# module_alu1_ctrl.net
KiCad netlist of a schematic drawn in EAGLE
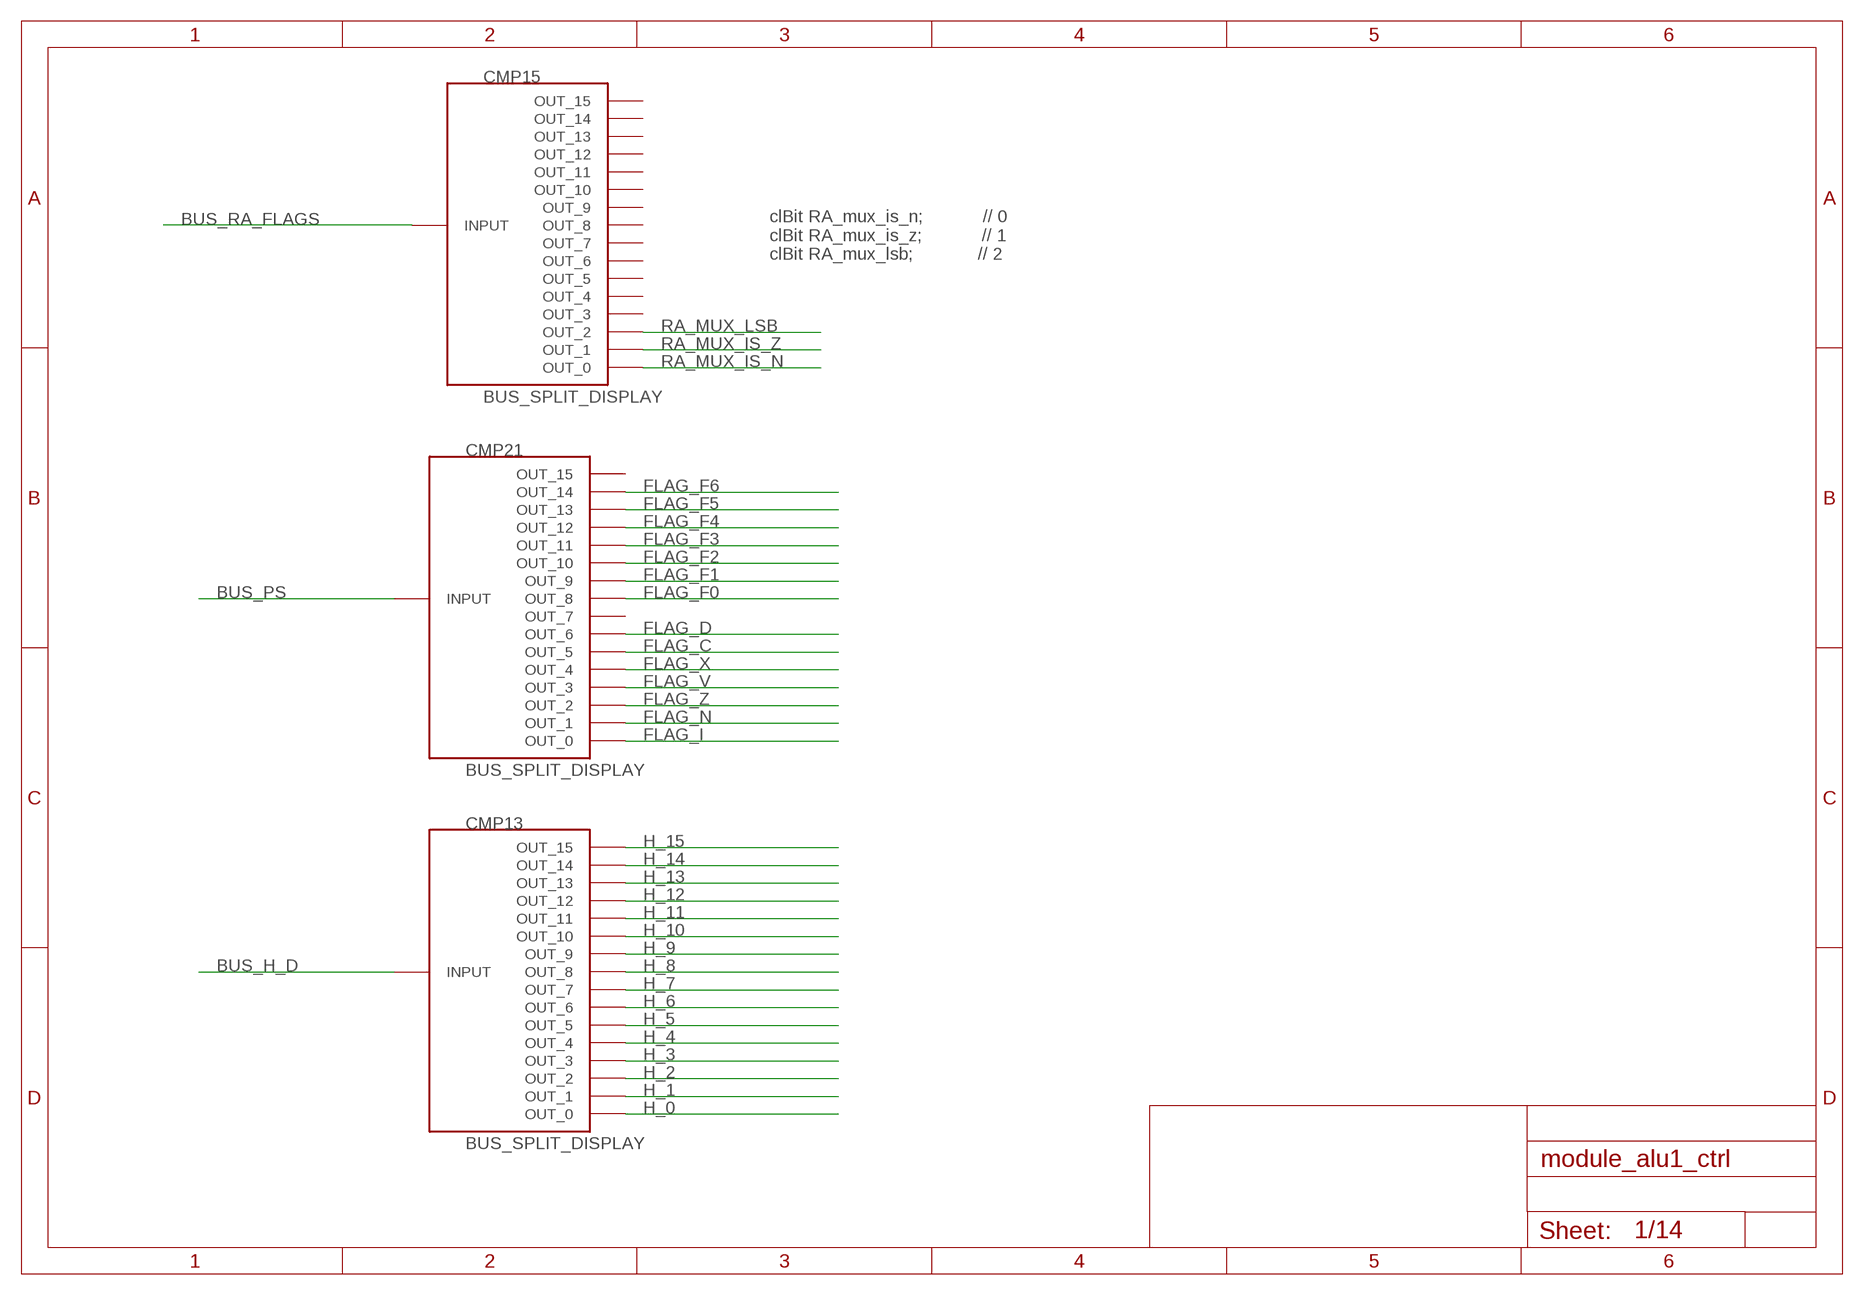
[diagram p0: schematic, sheet 1]
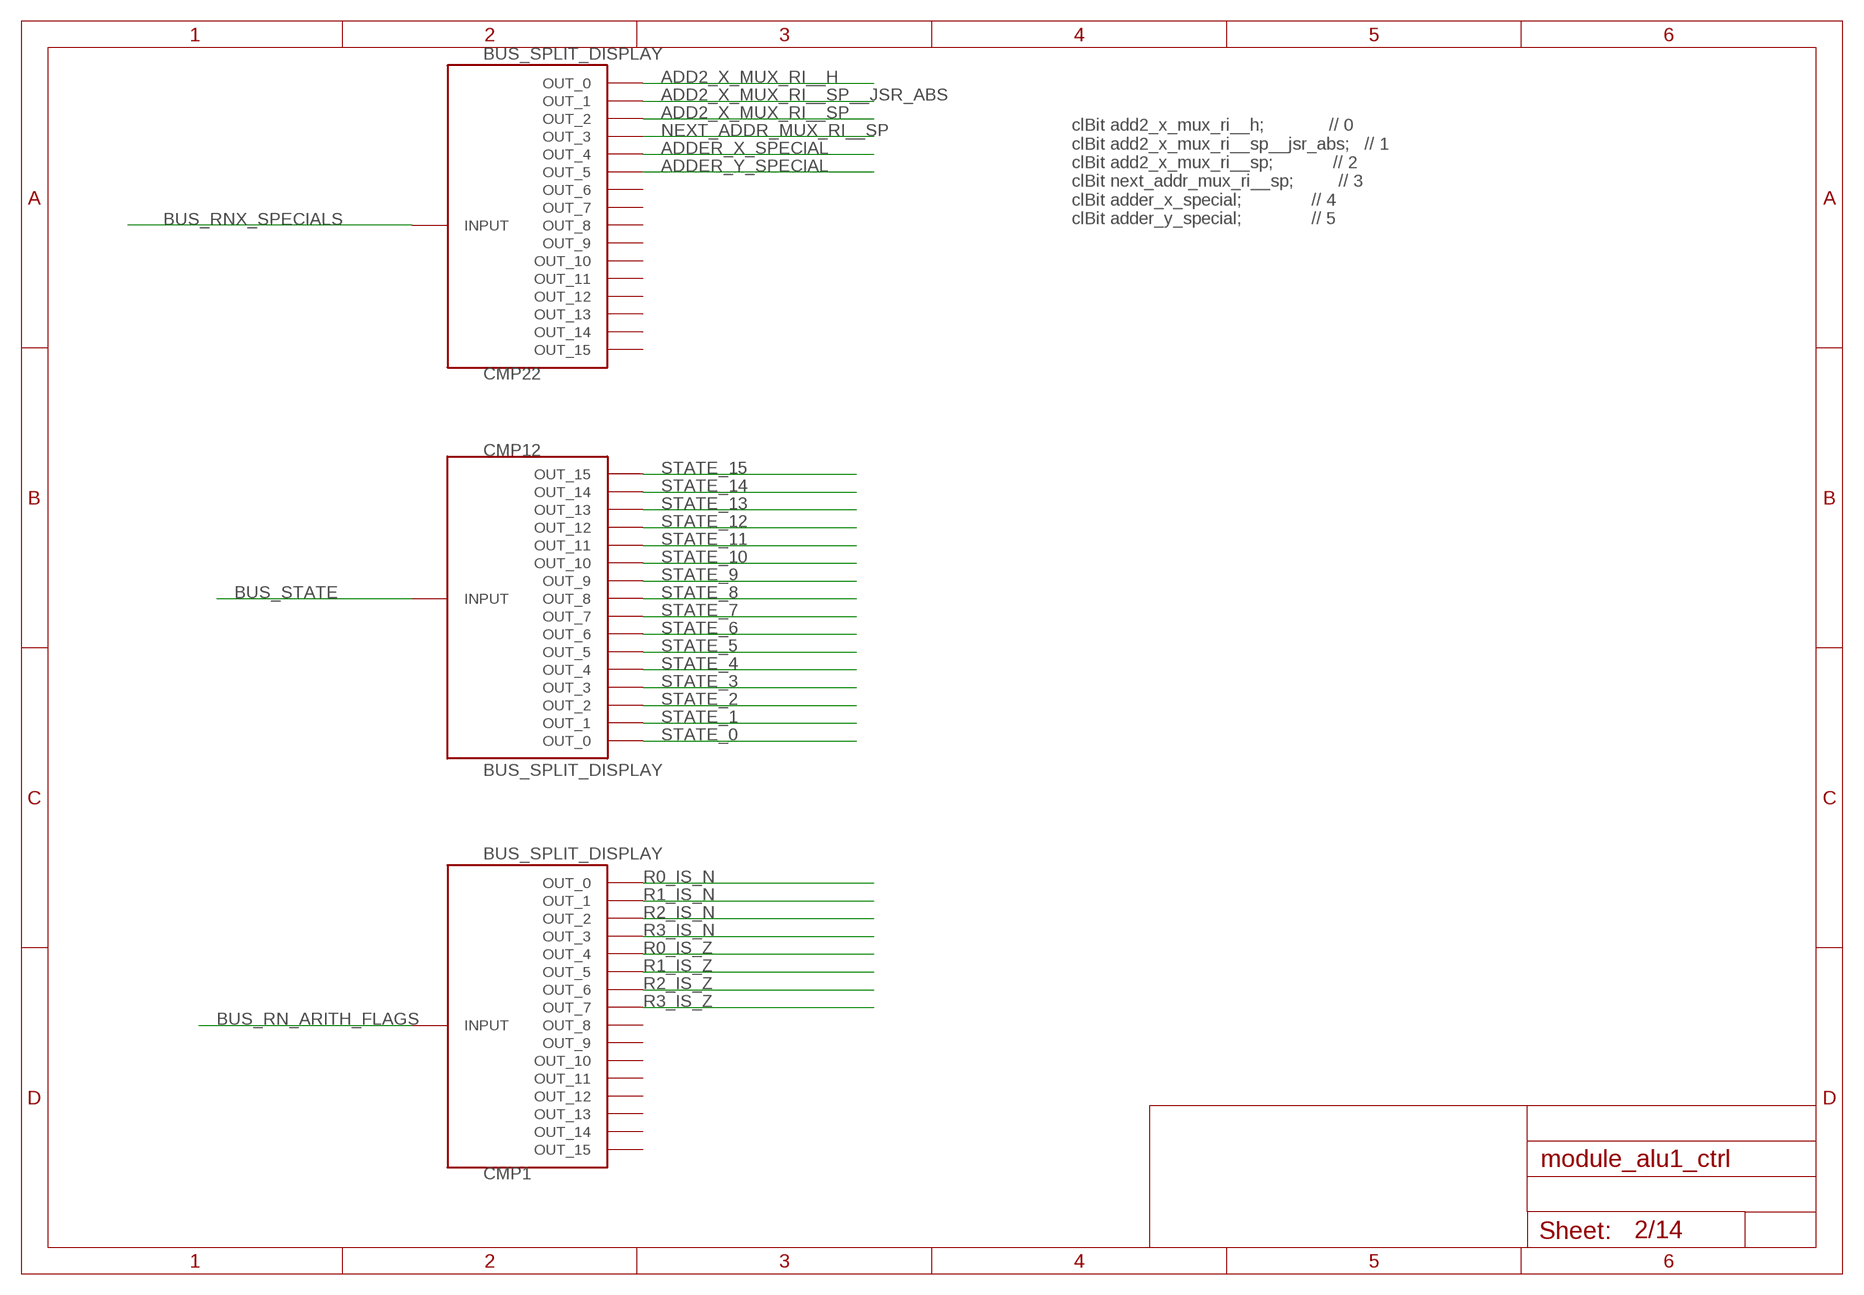
[diagram p1: schematic, sheet 2]
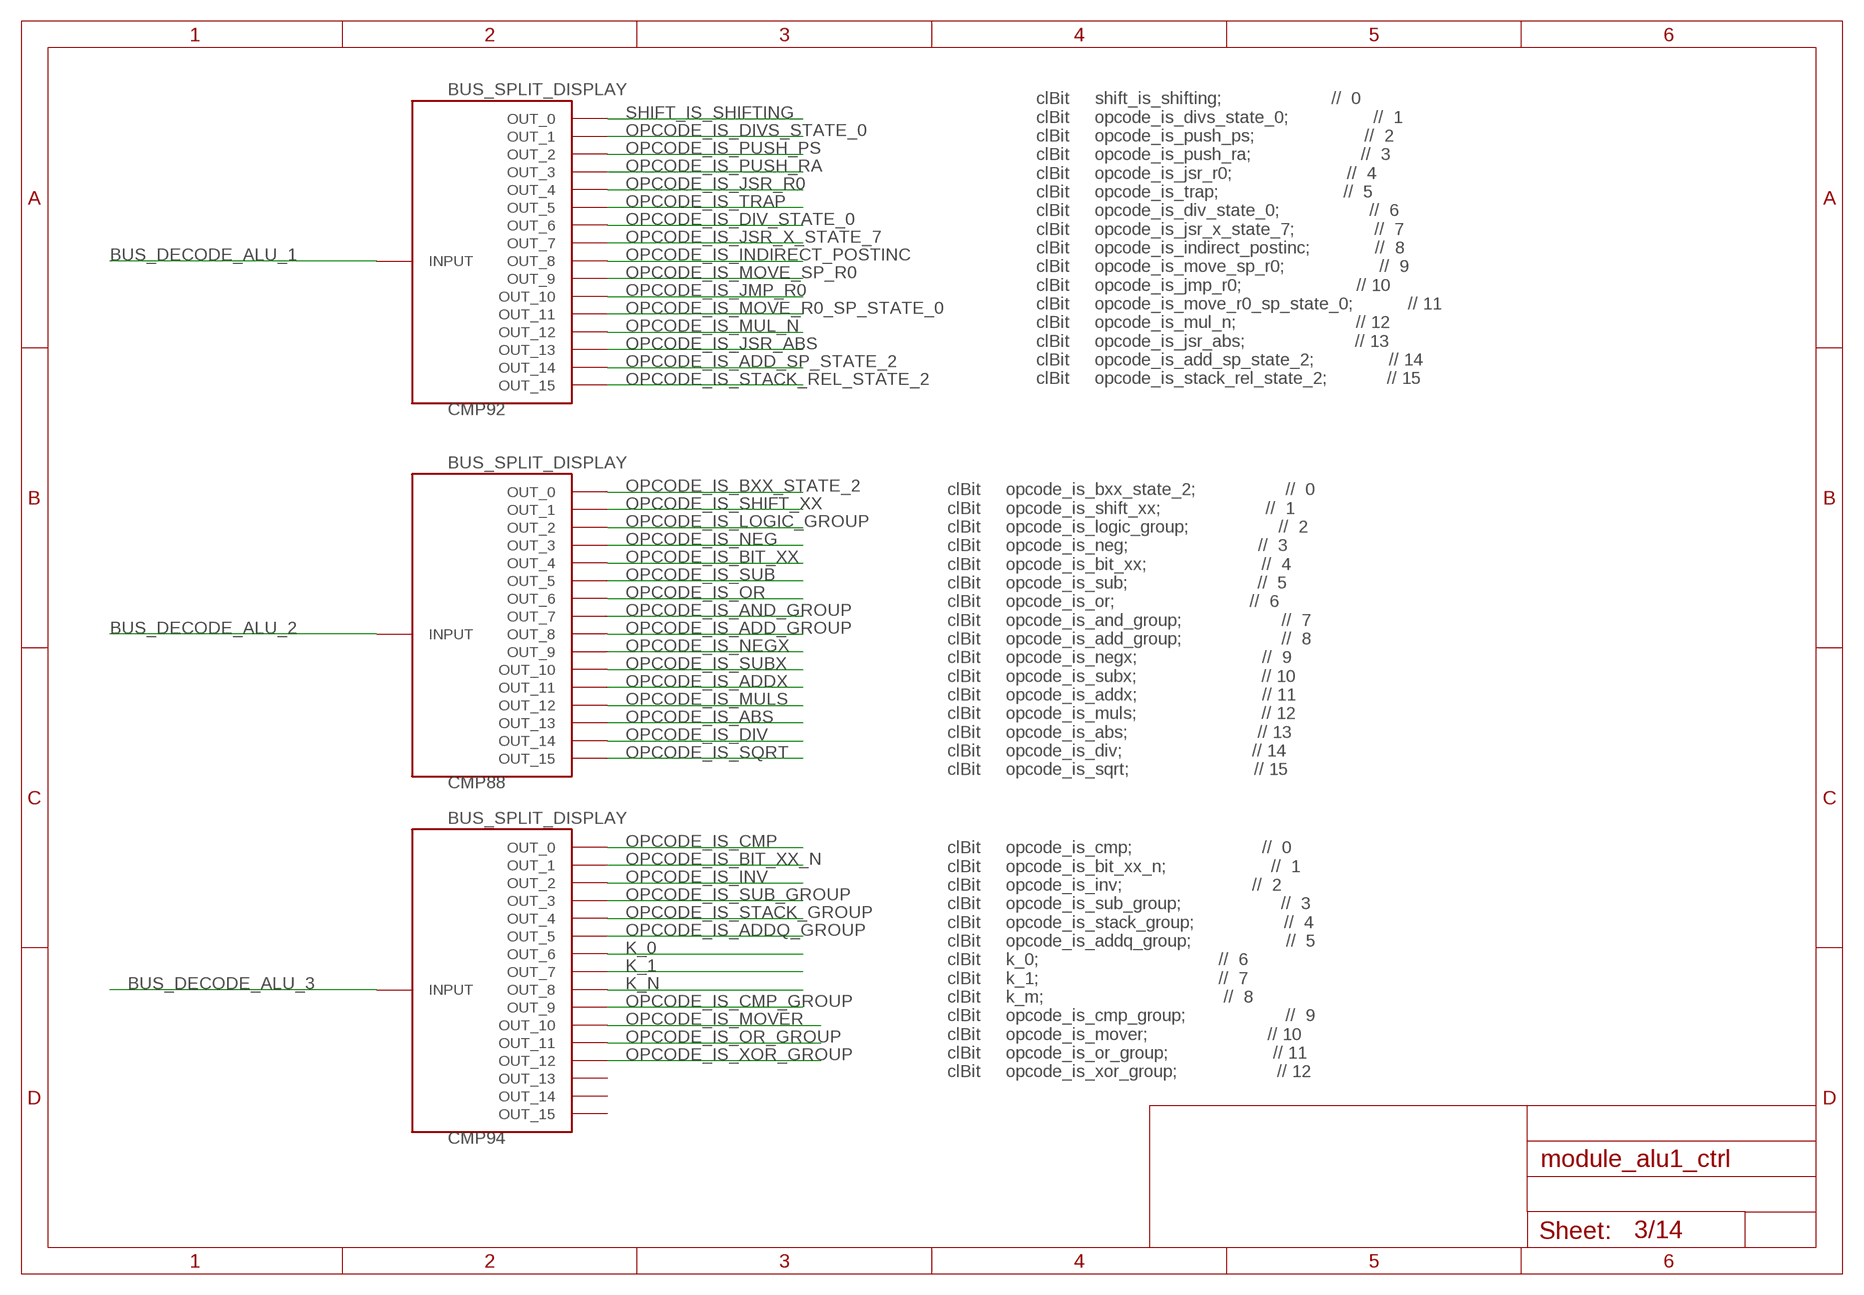
[diagram p2: schematic, sheet 3]
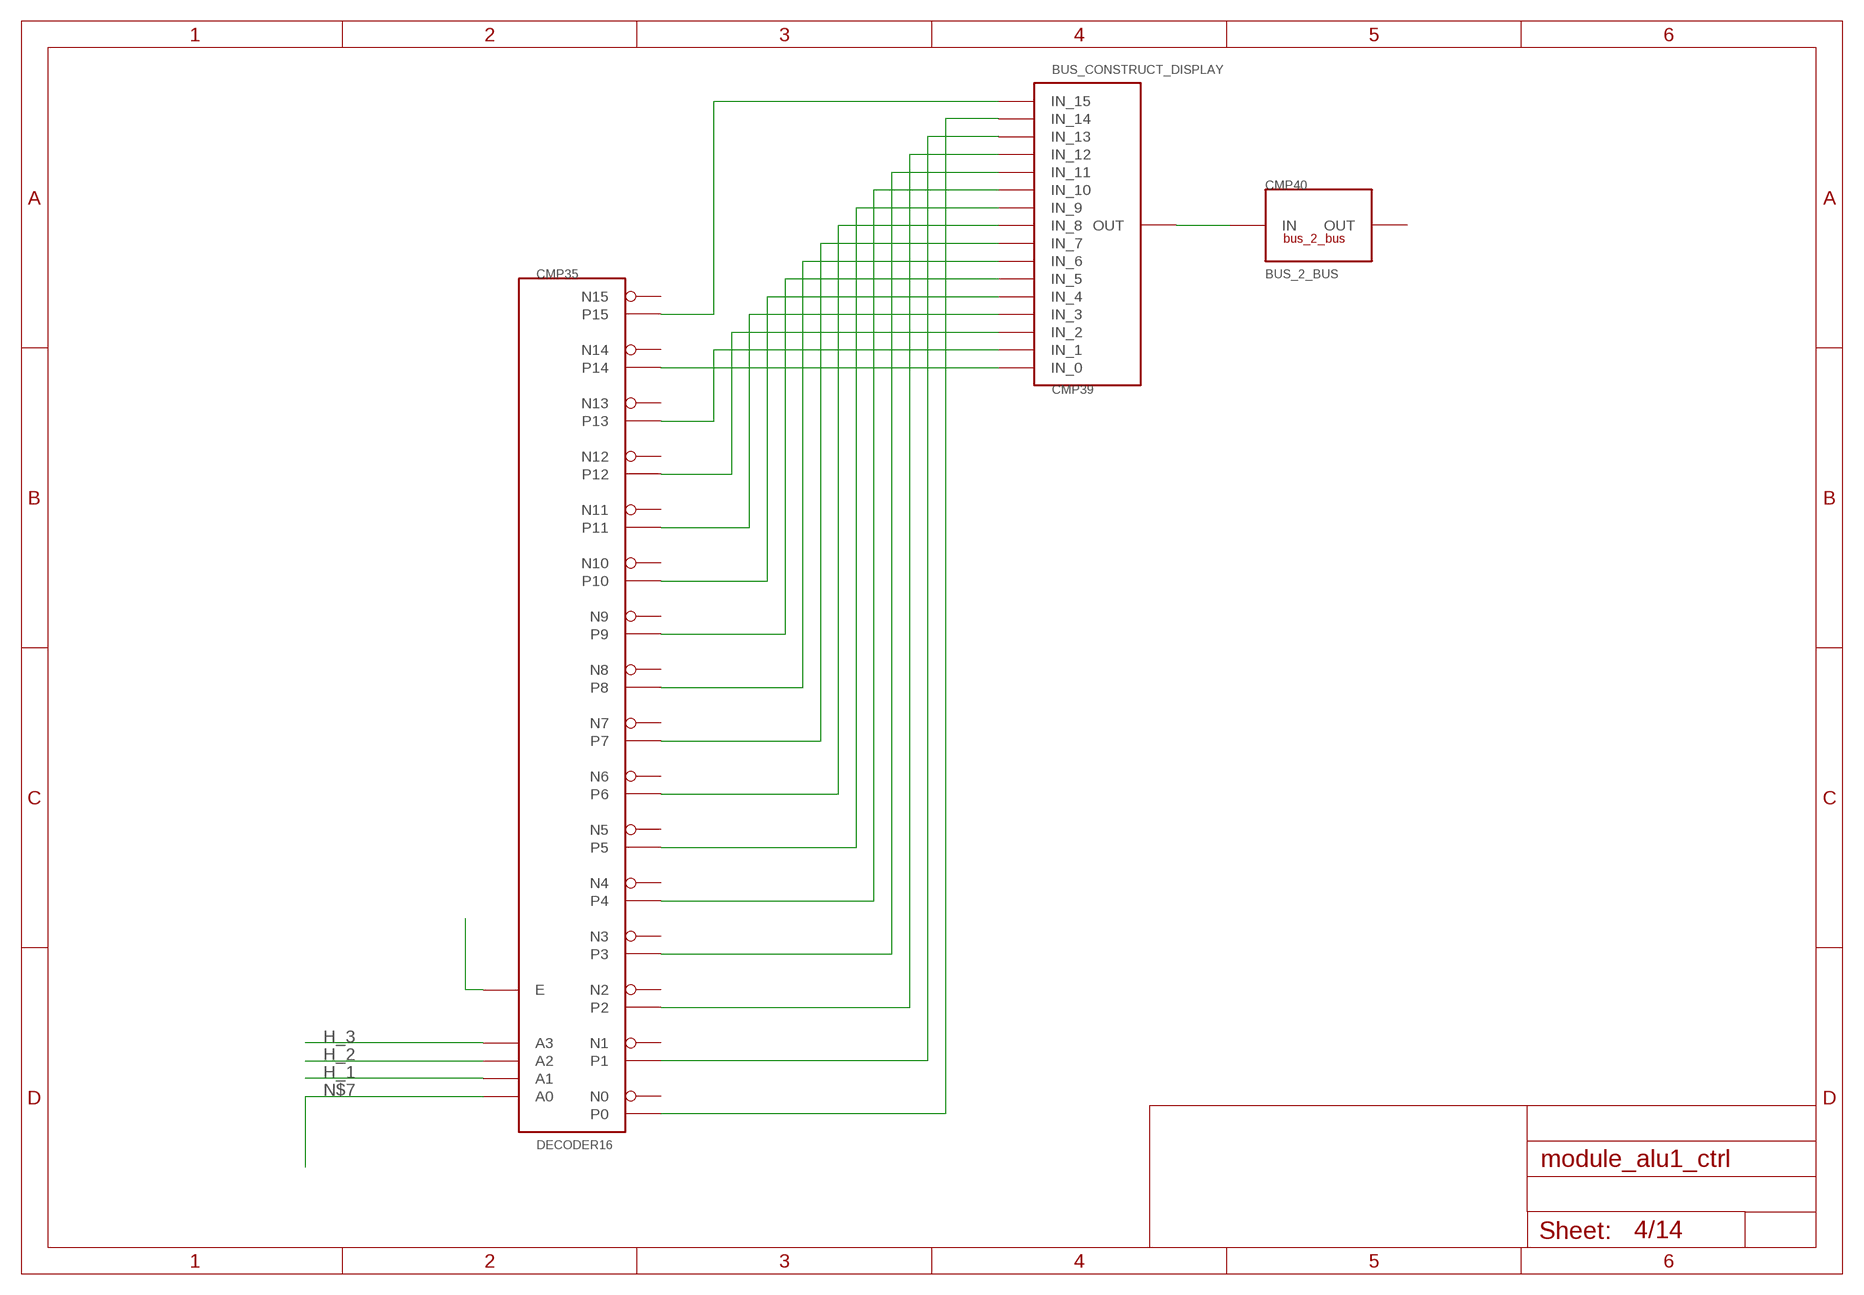
[diagram p3: schematic, sheet 4]
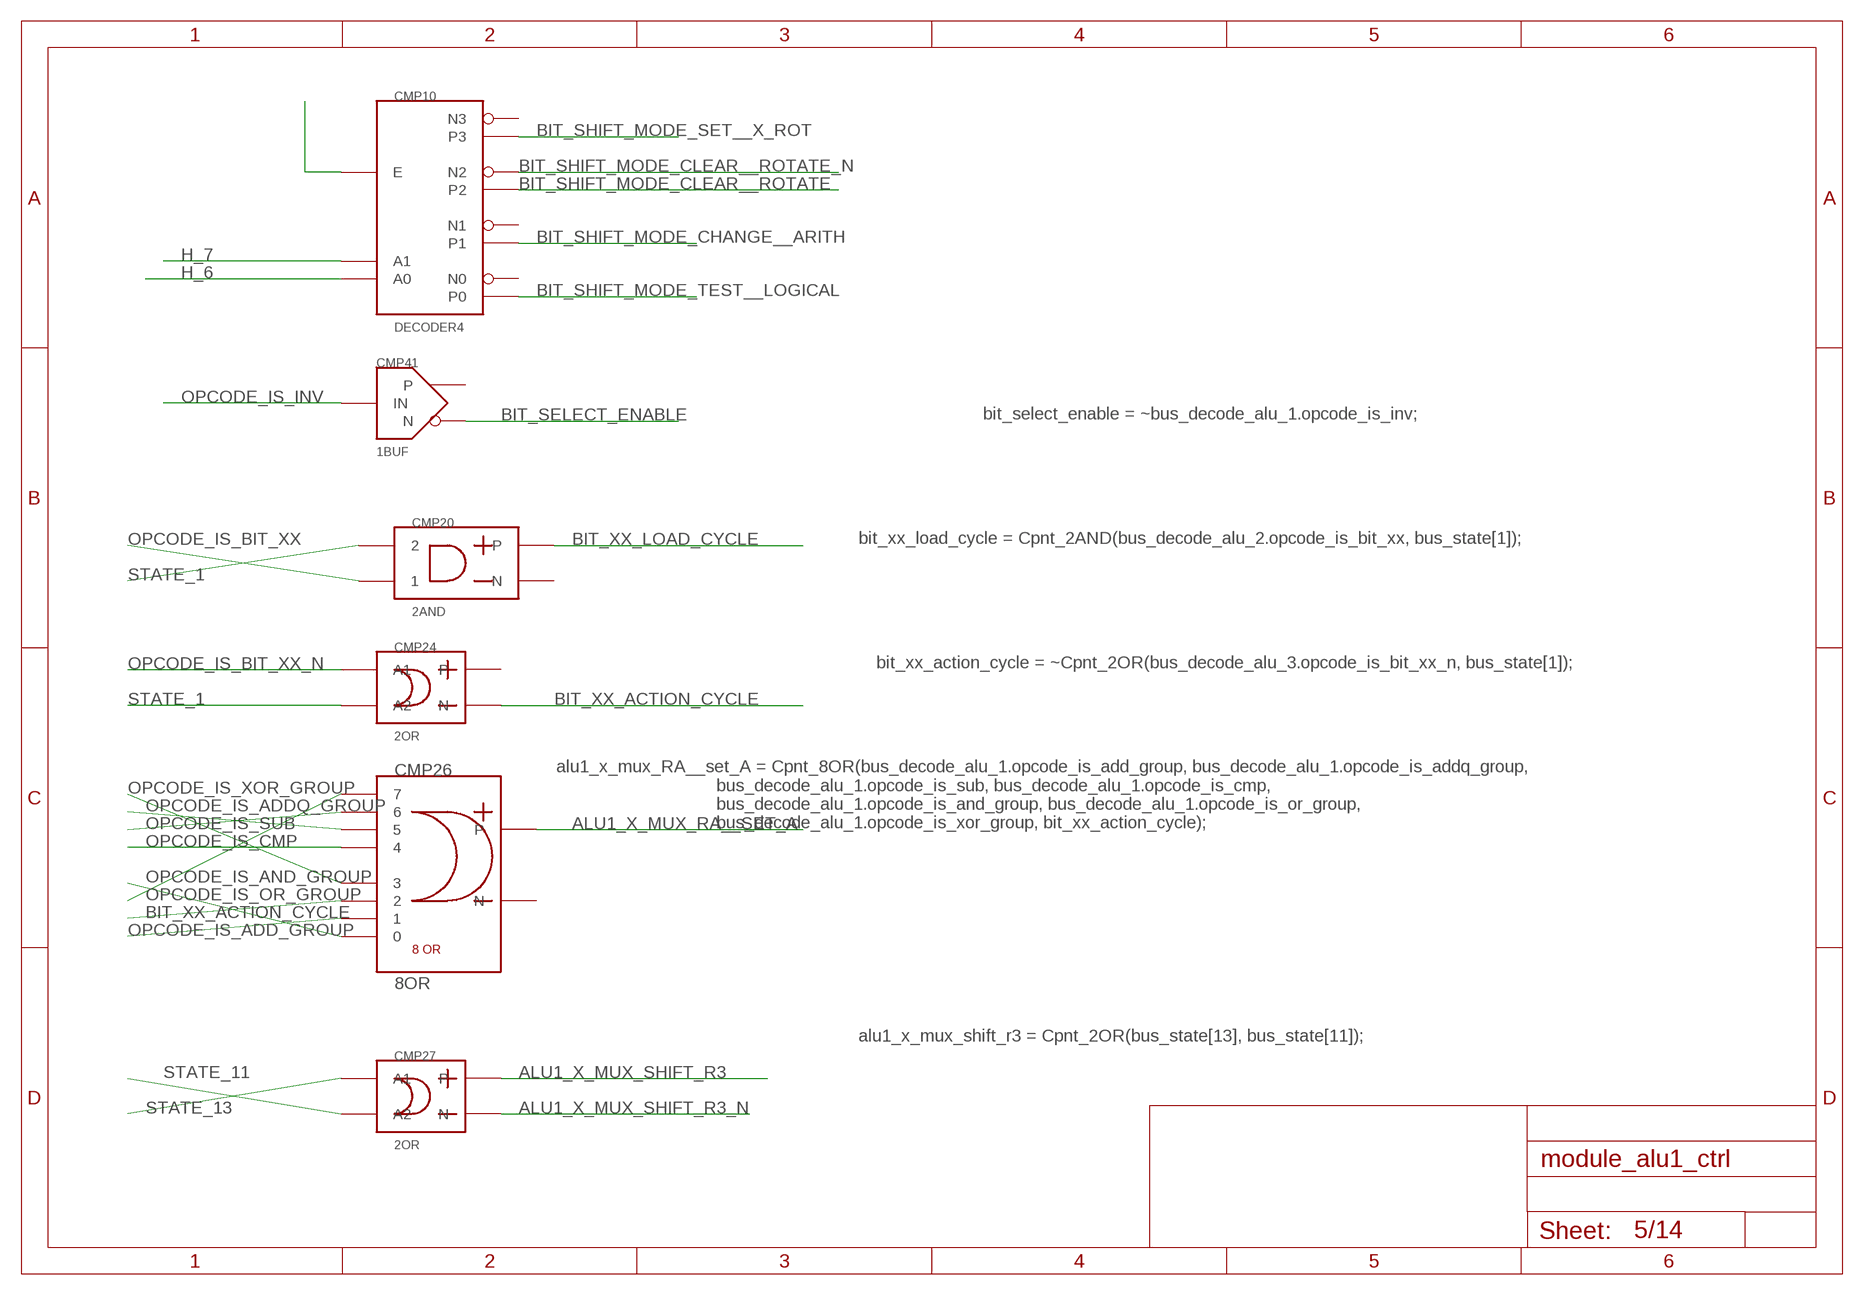
[diagram p4: schematic, sheet 5]
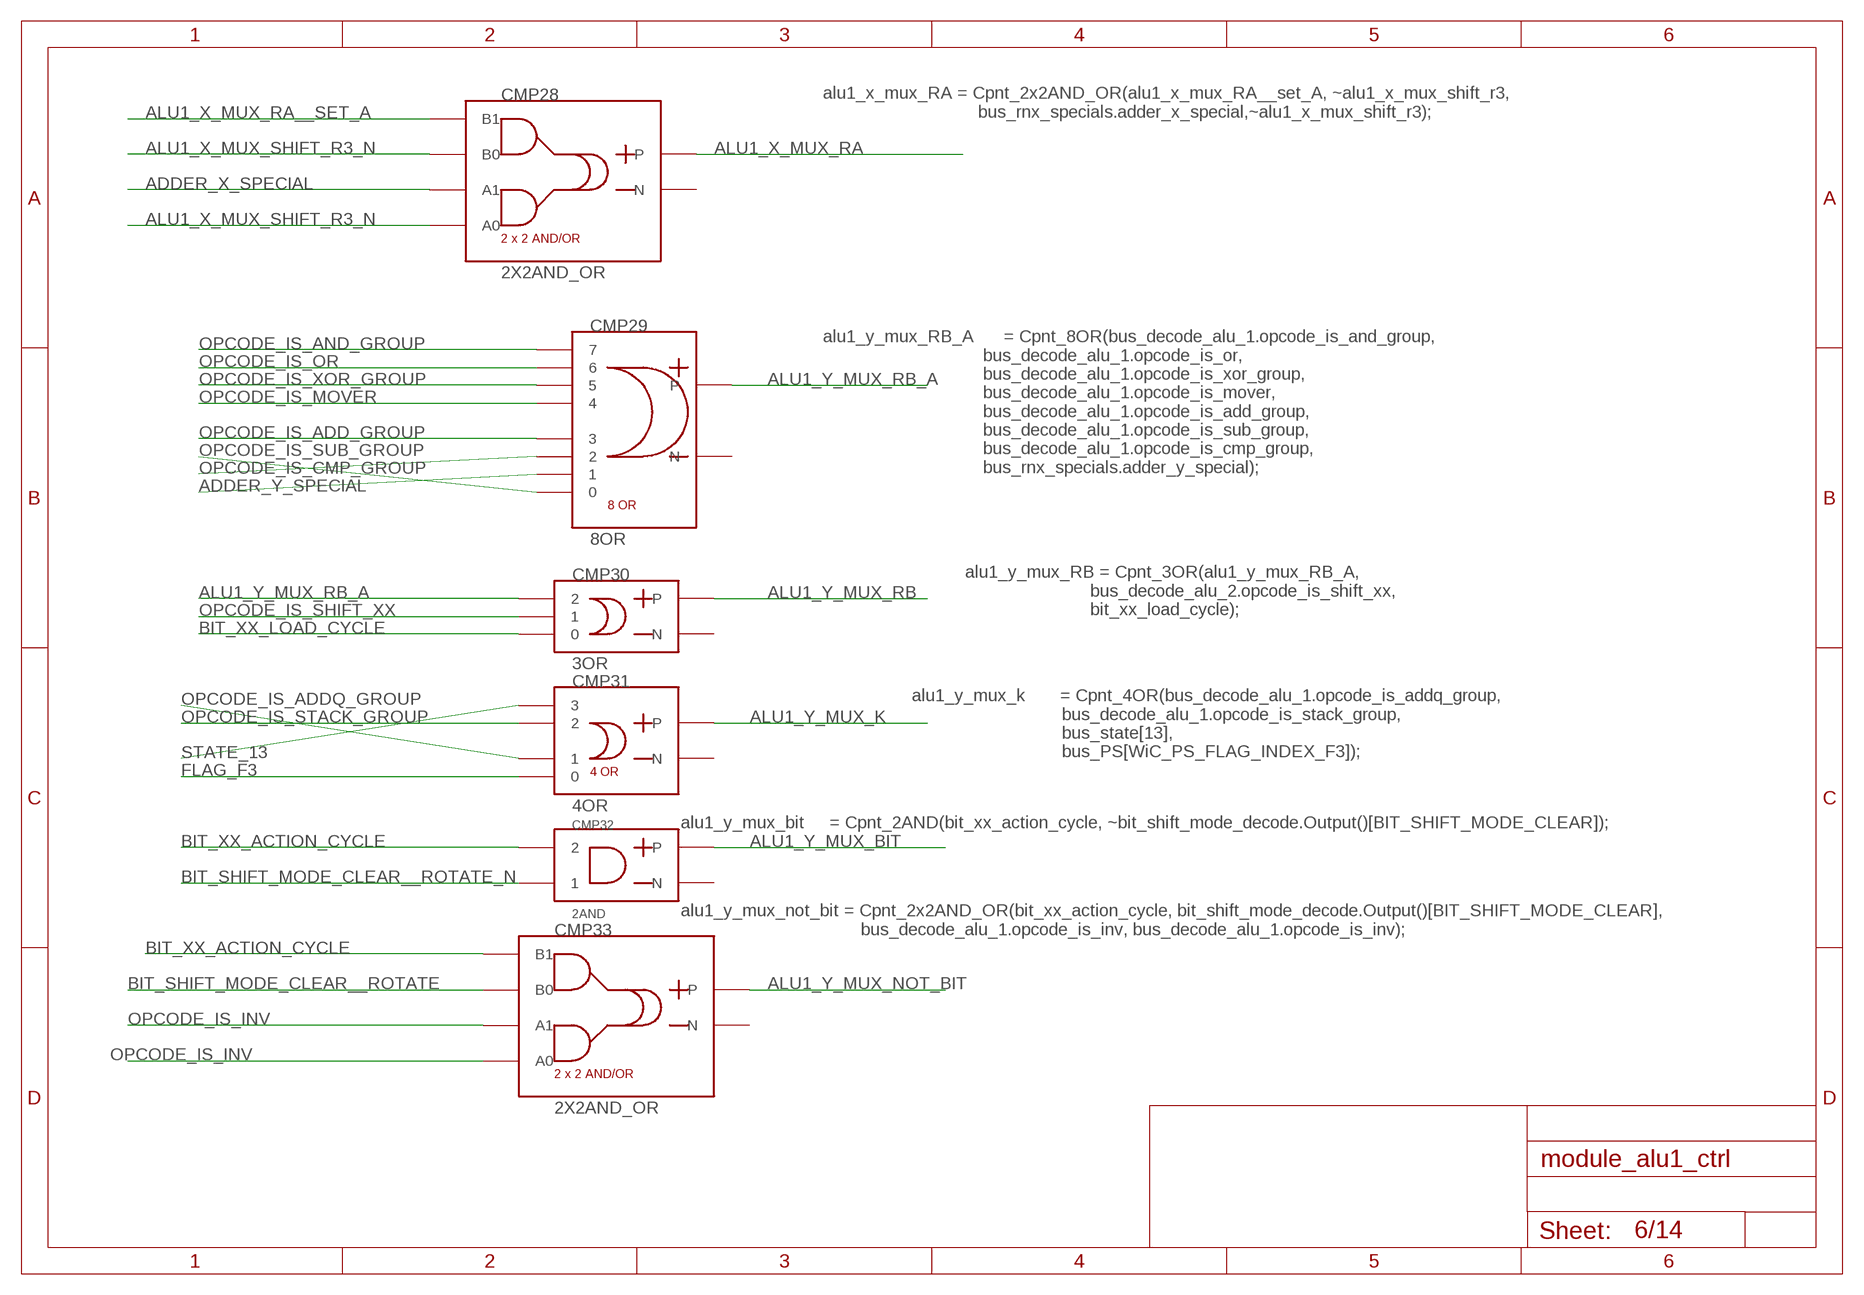
[diagram p5: schematic, sheet 6]
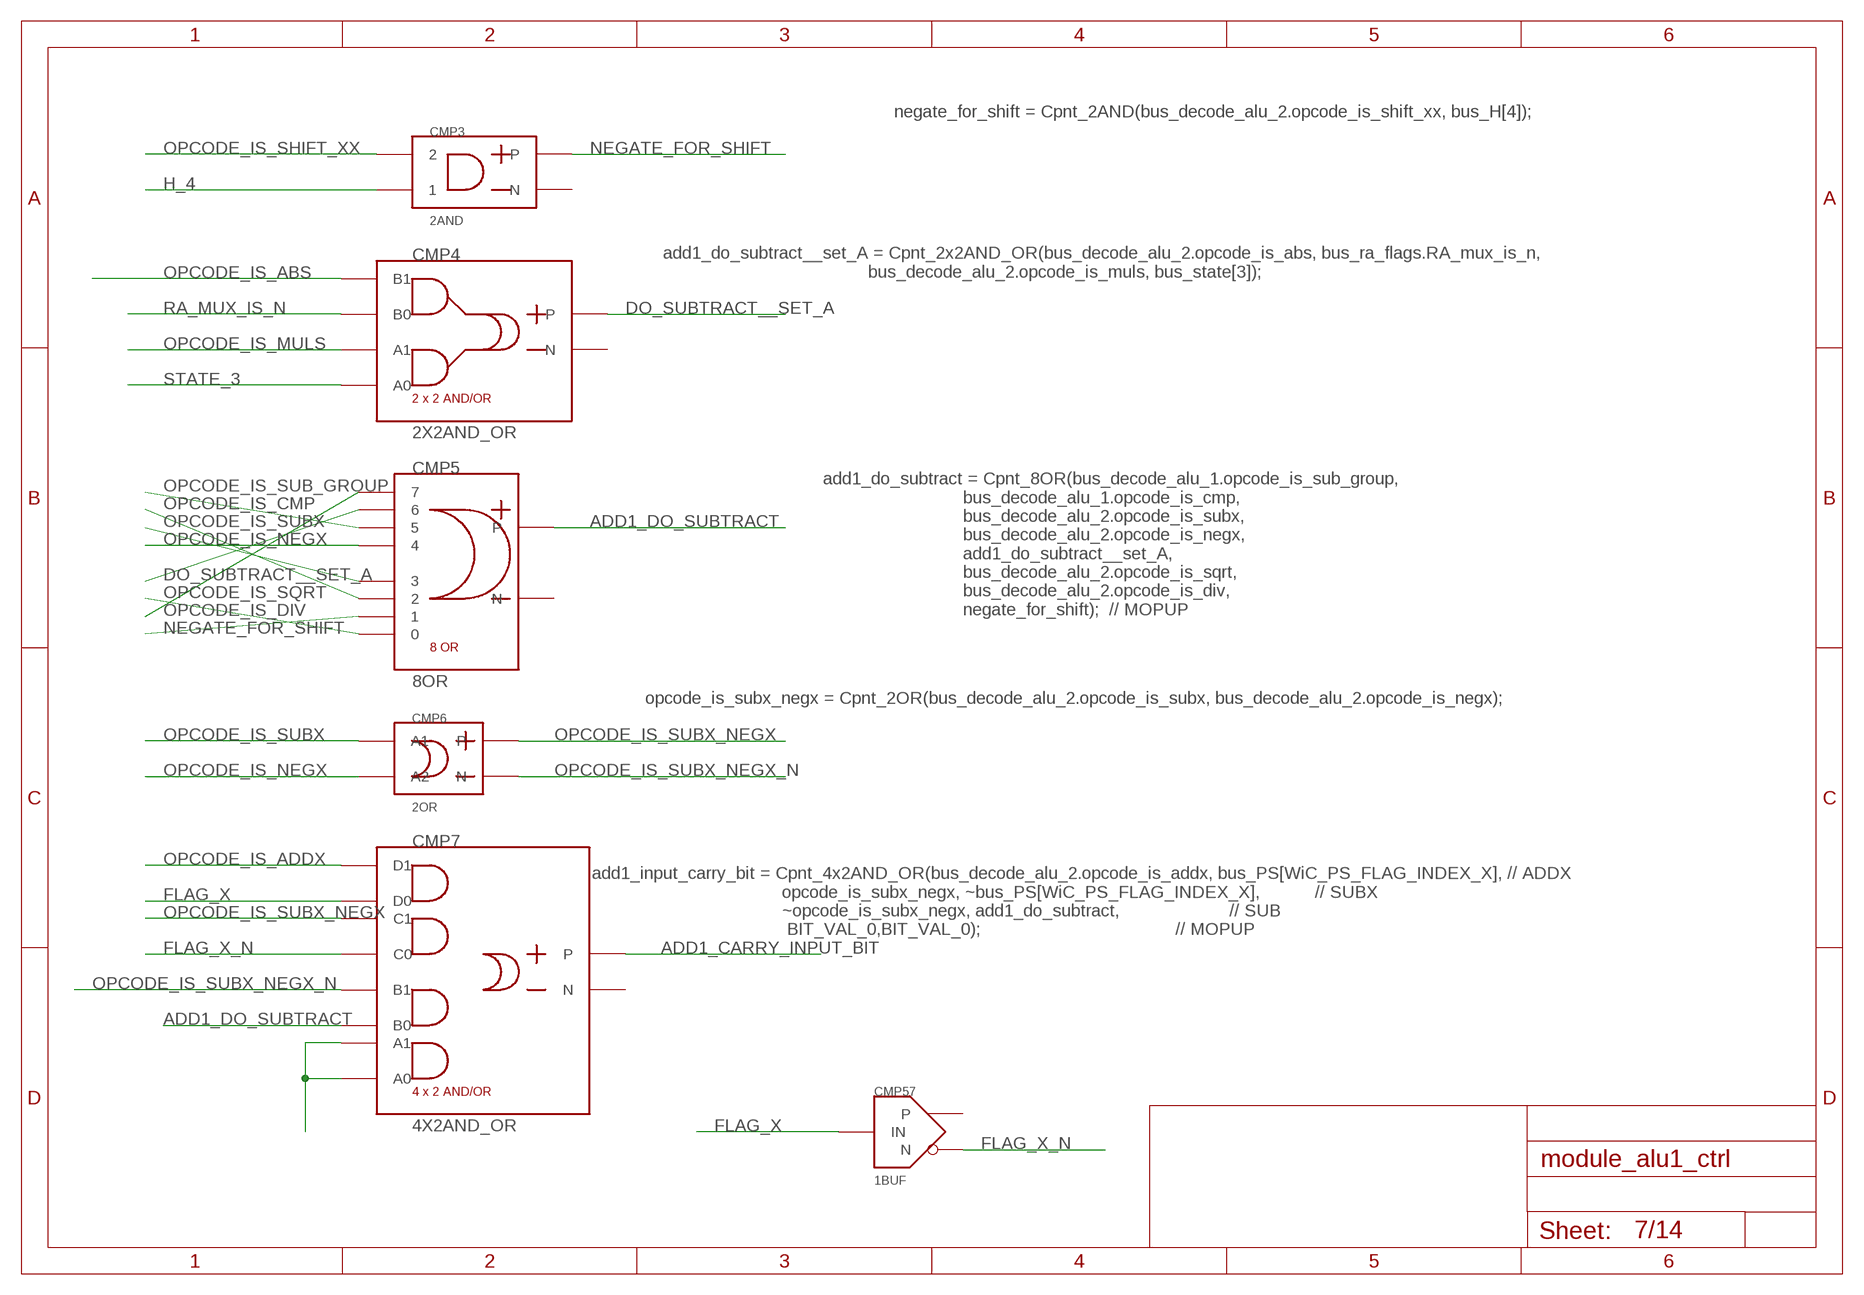
[diagram p6: schematic, sheet 7]
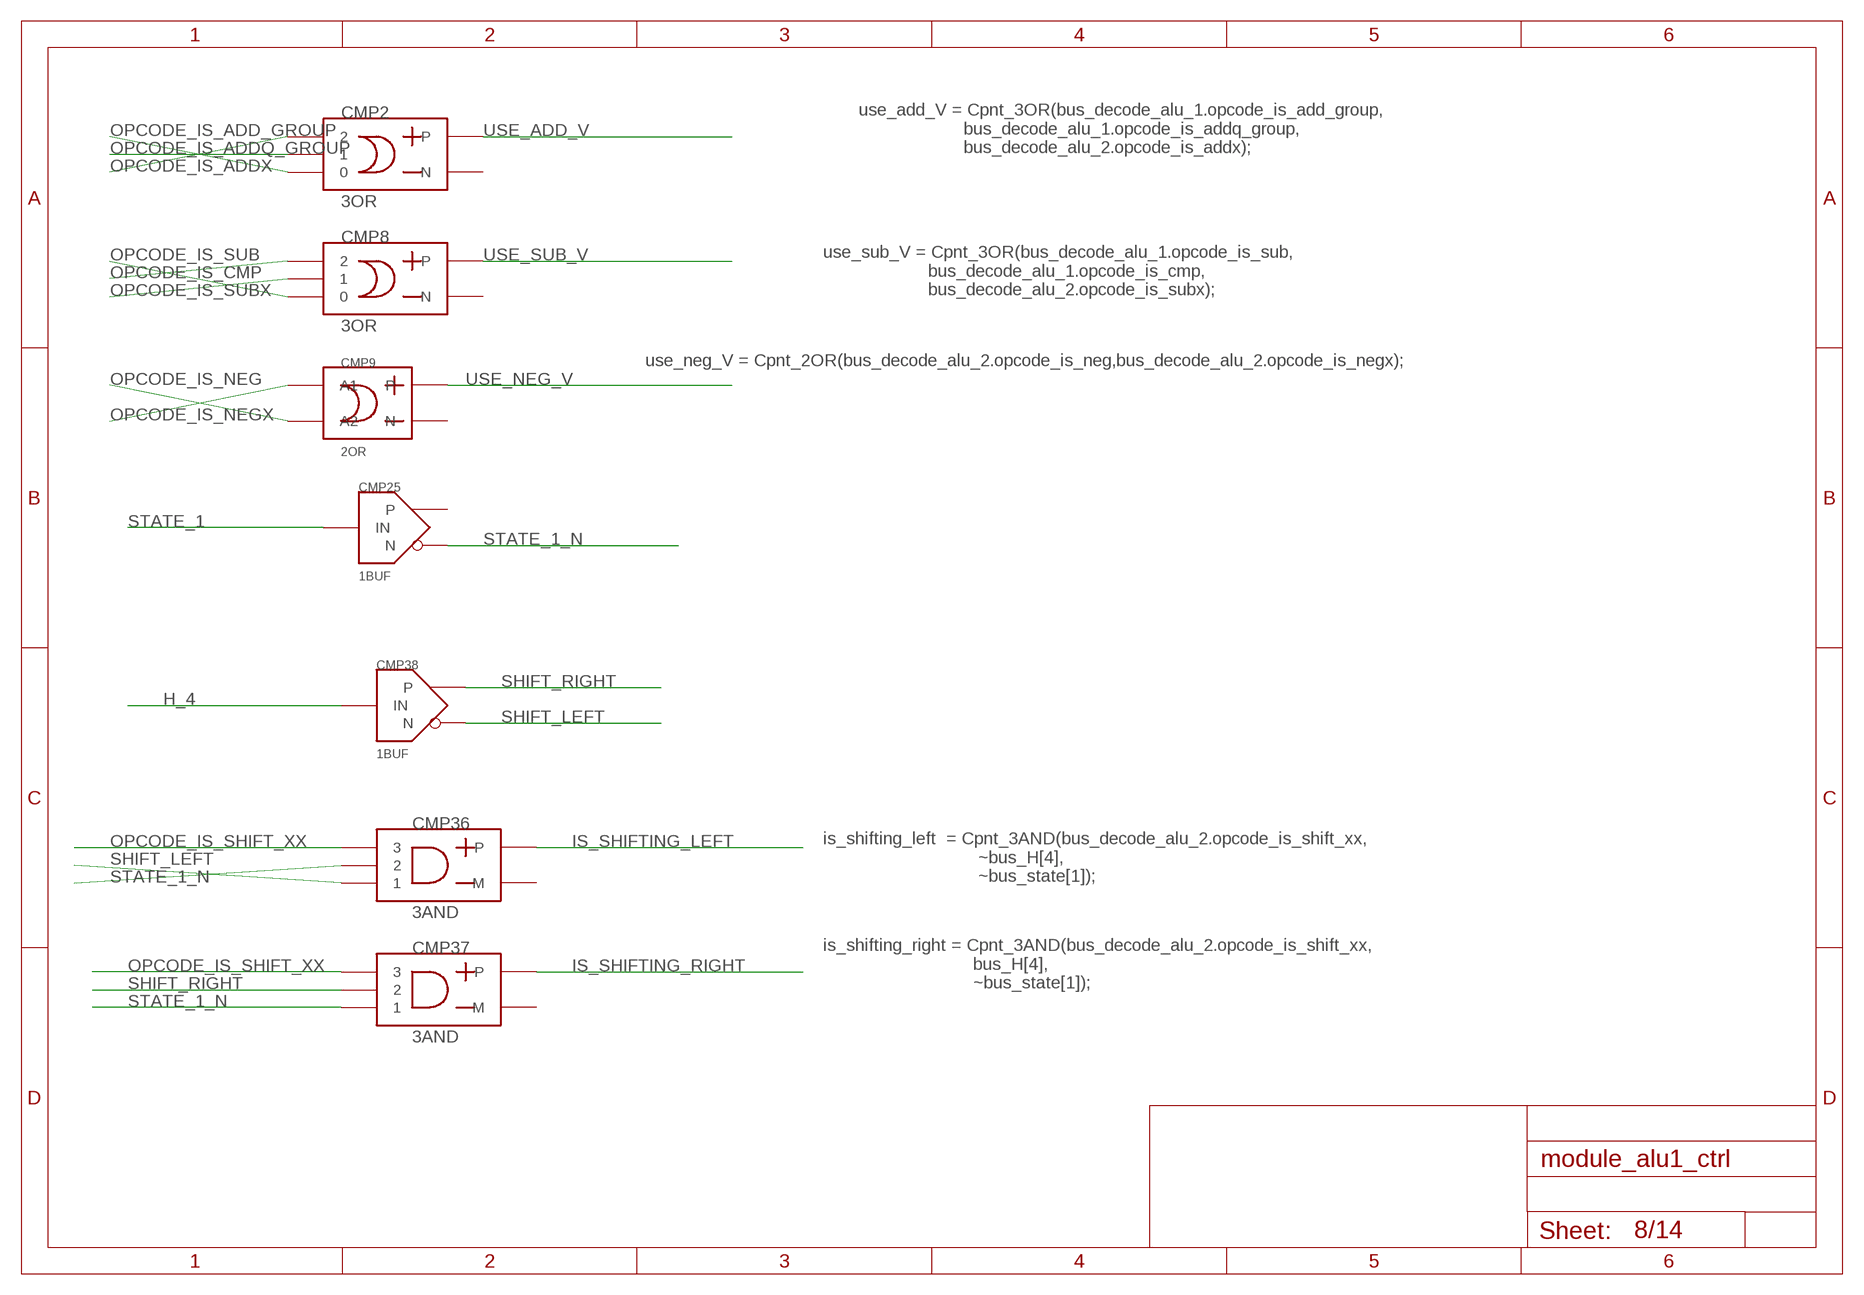
[diagram p7: schematic, sheet 8]
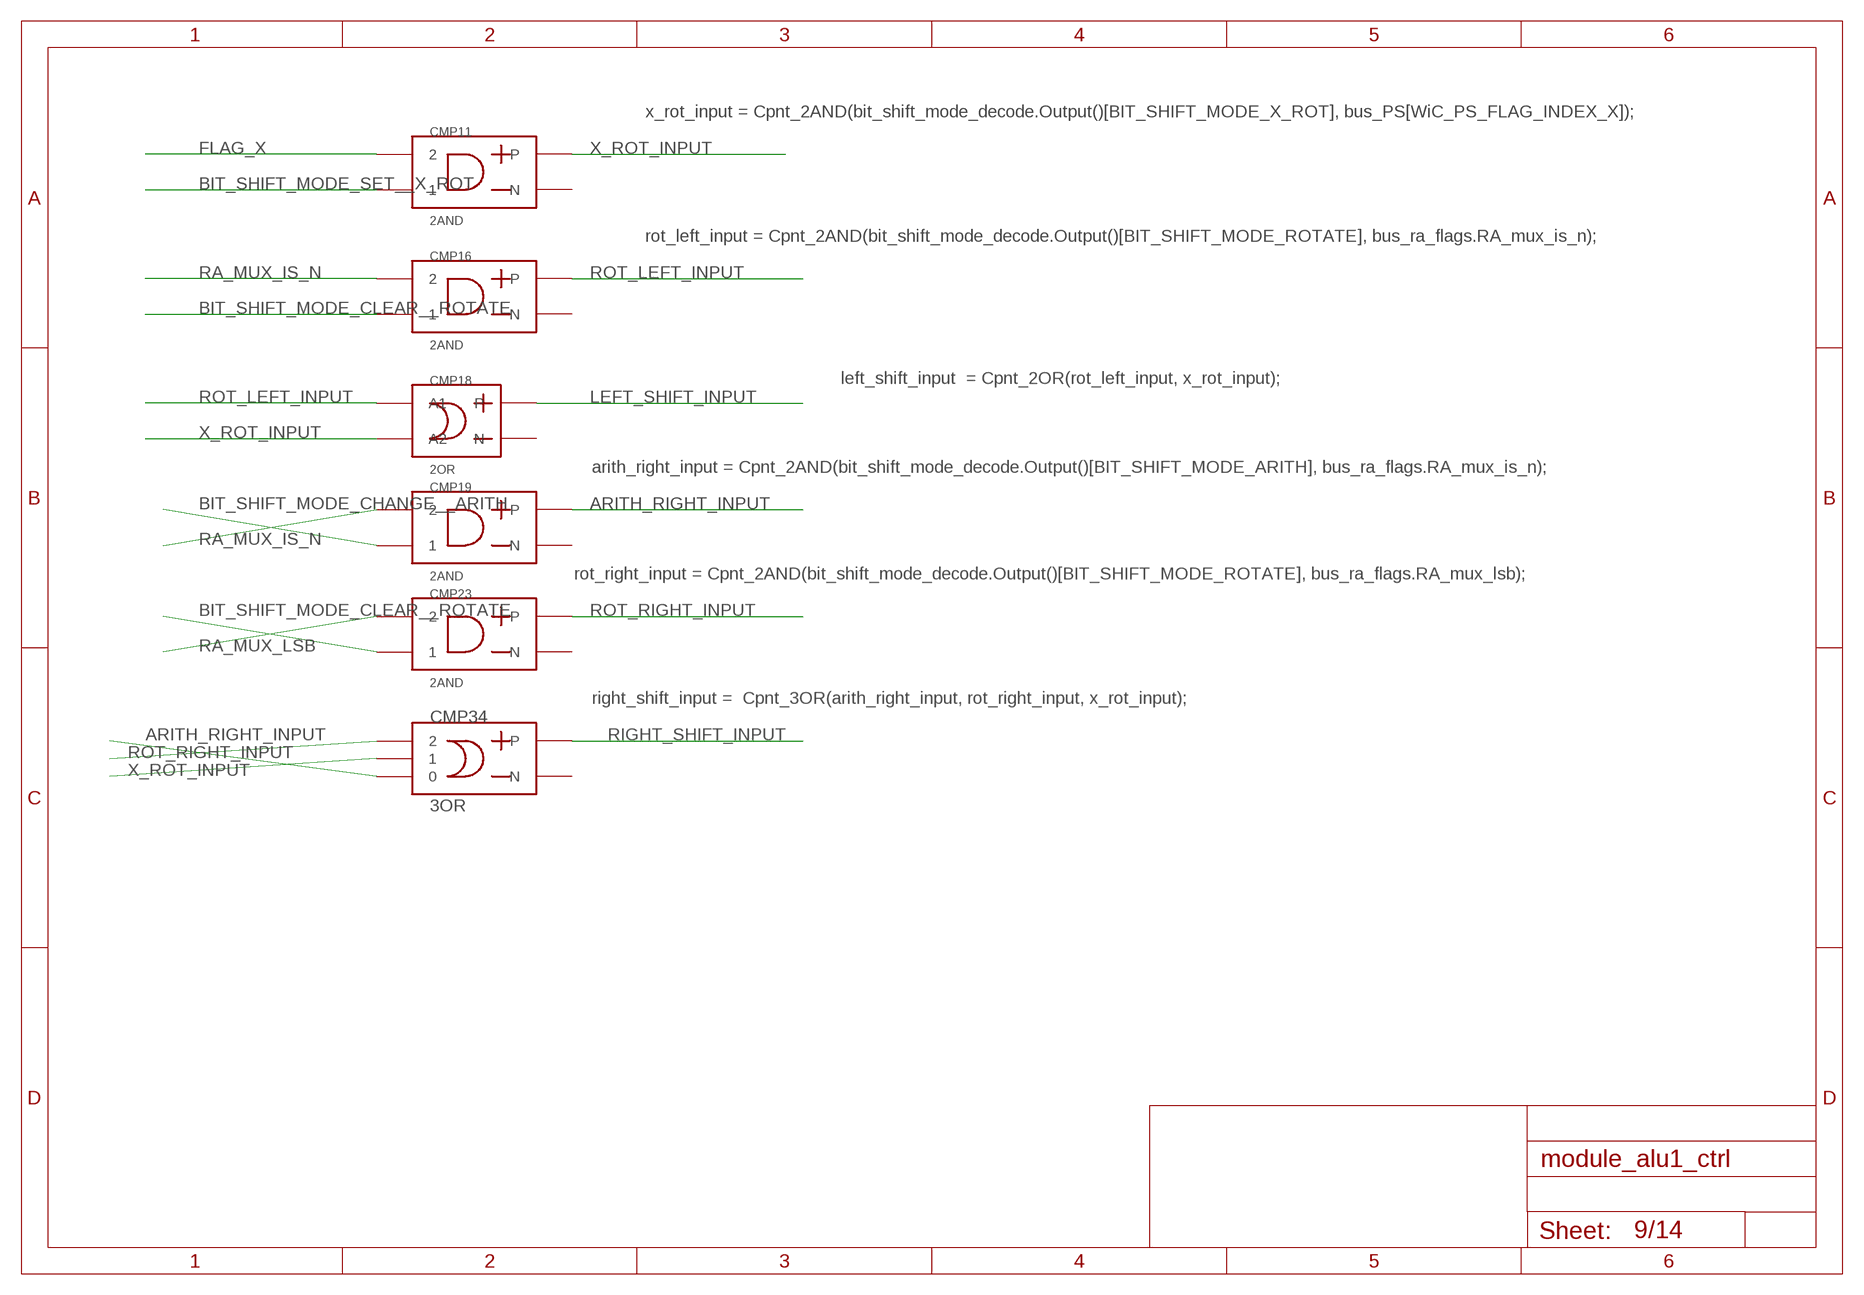
[diagram p8: schematic, sheet 9]
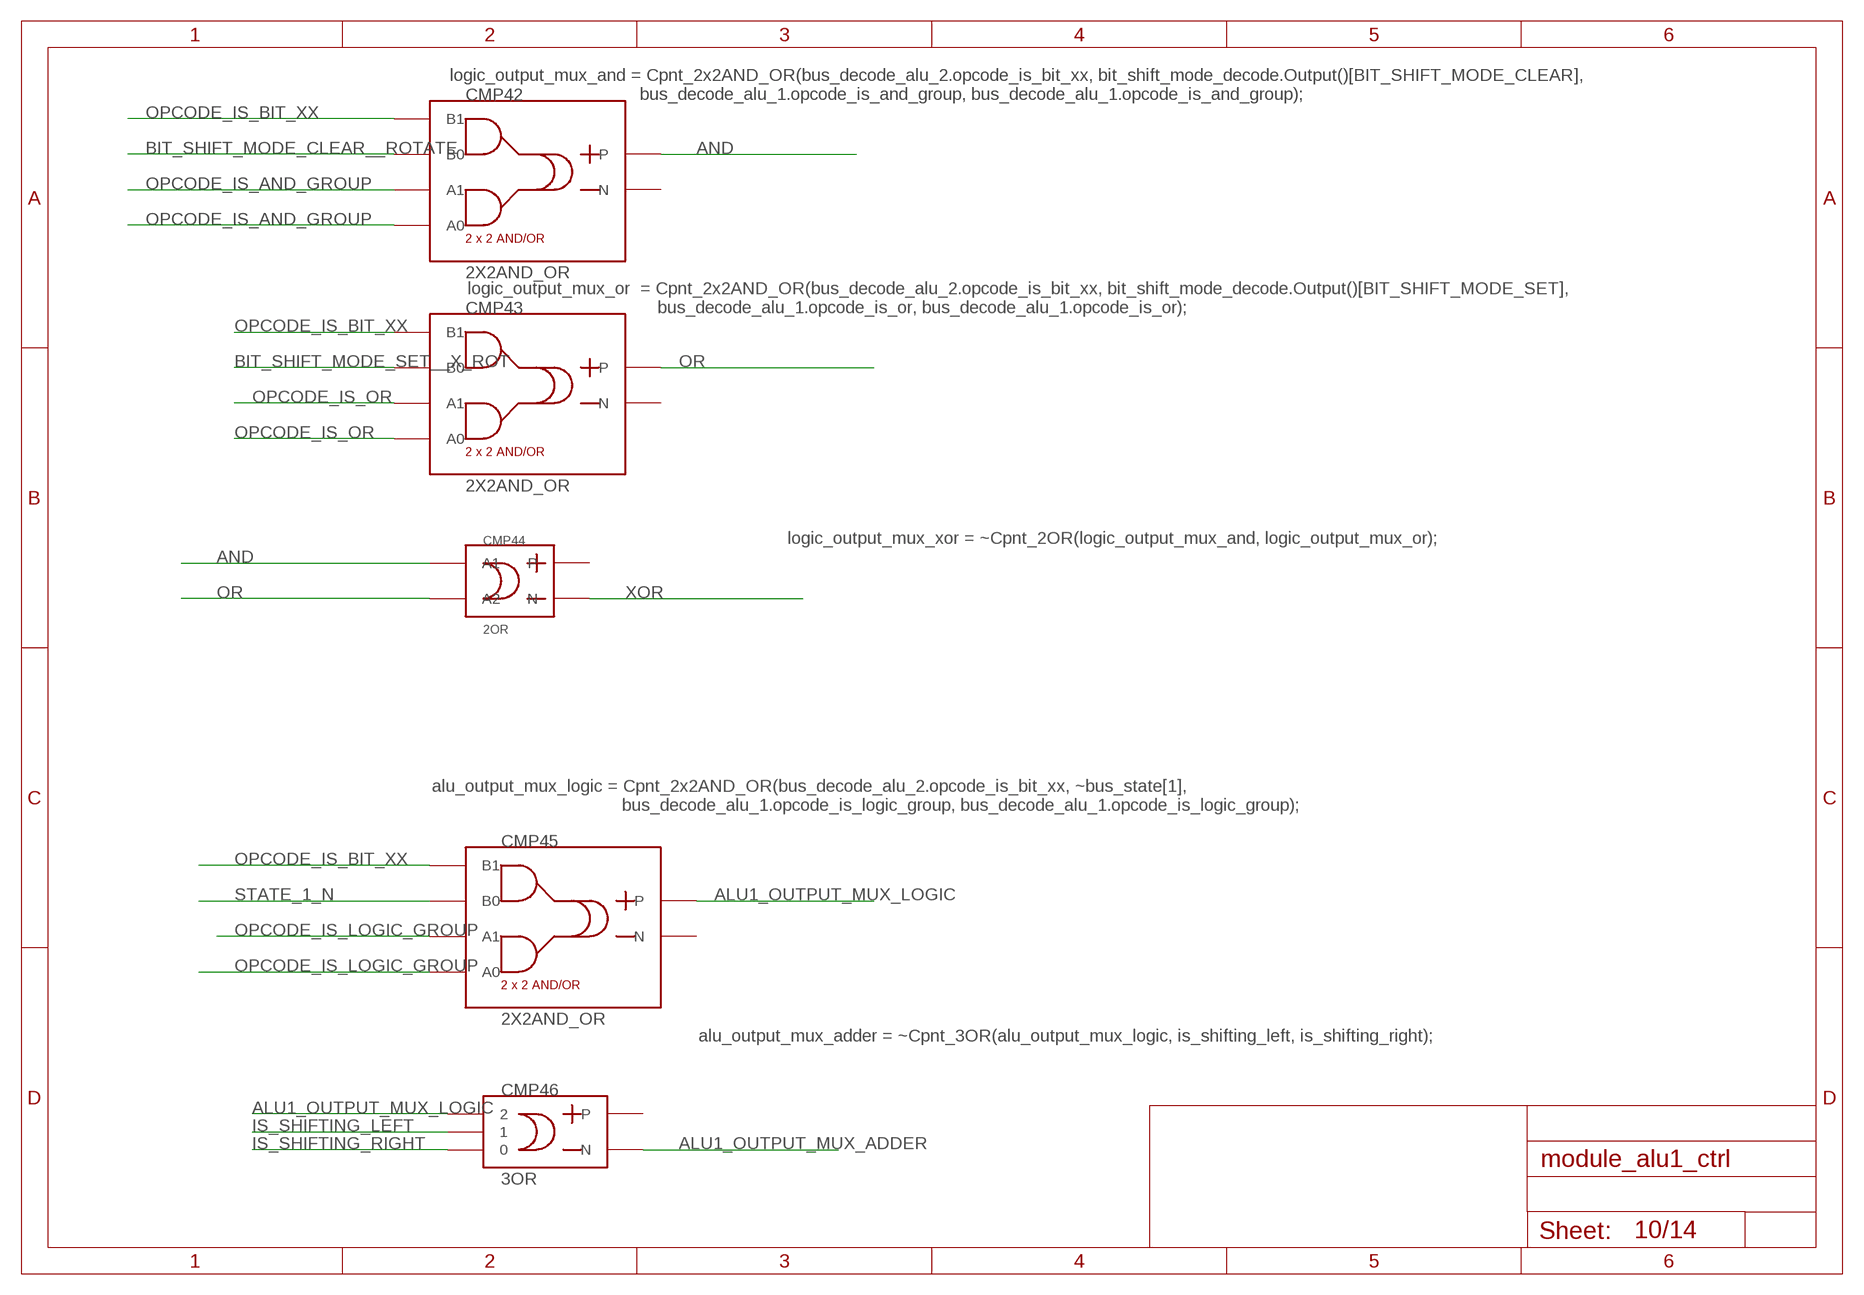
[diagram p9: schematic, sheet 10]
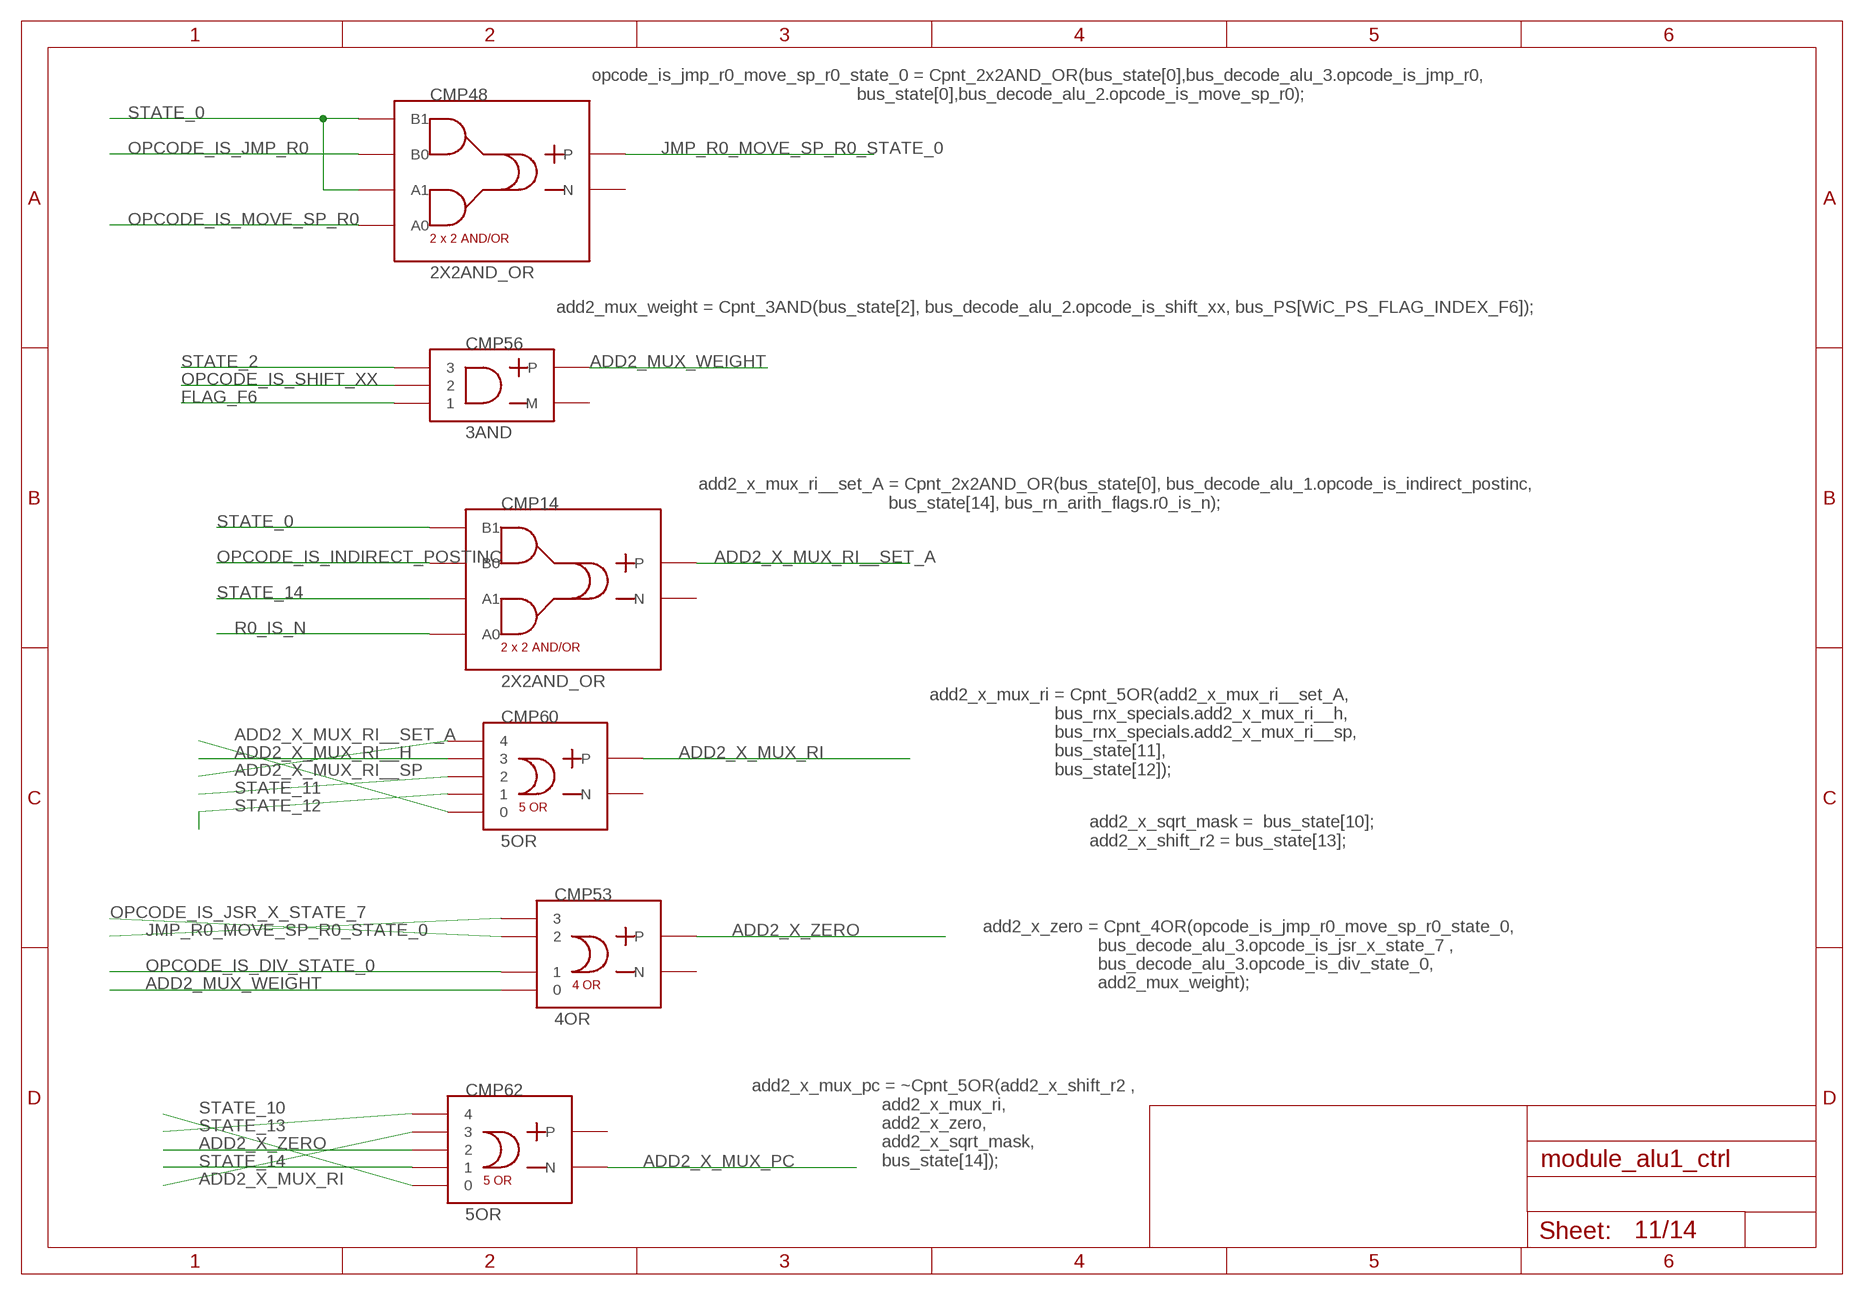
[diagram p10: schematic, sheet 11]
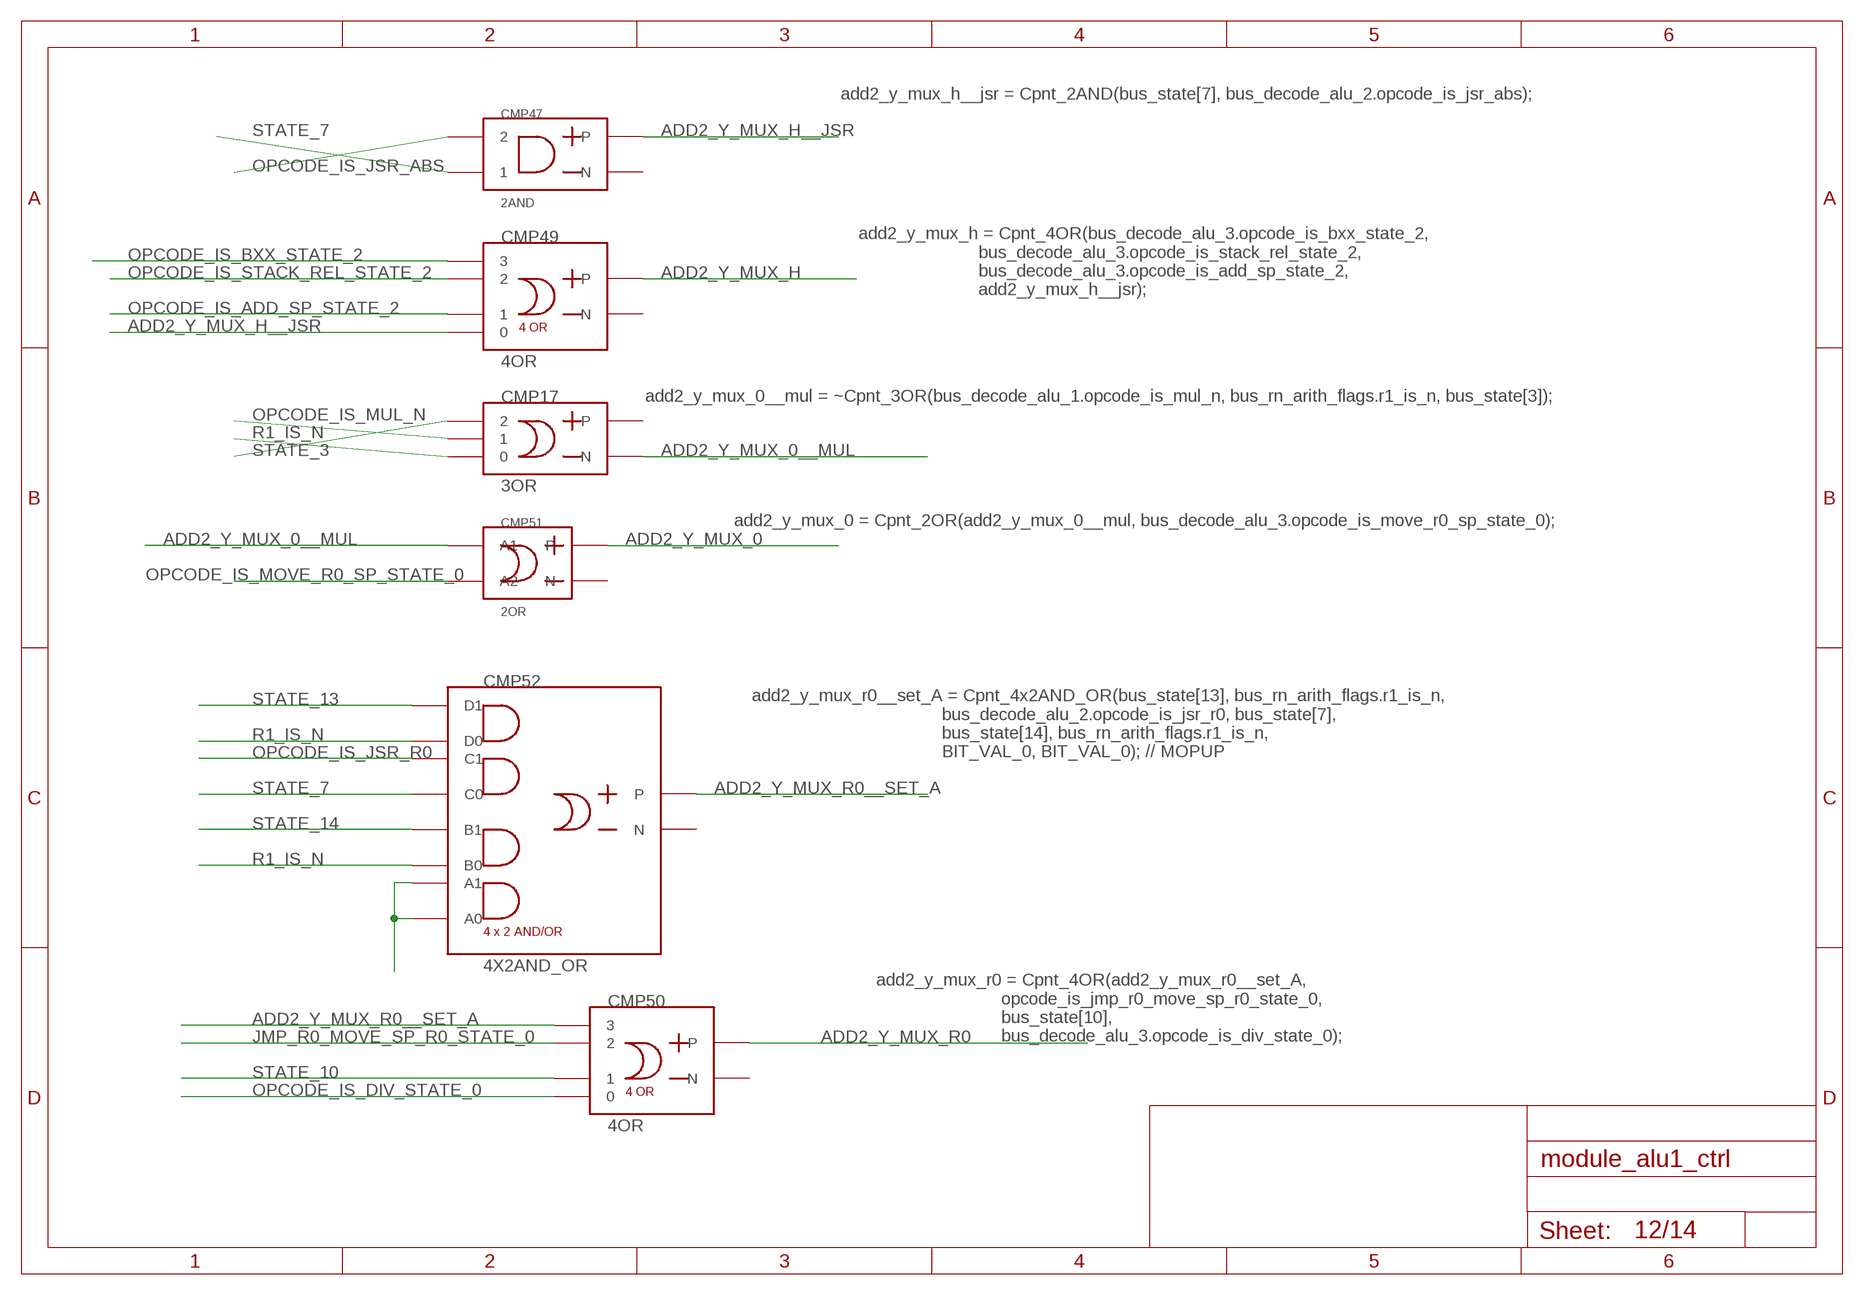
[diagram p11: schematic, sheet 12]
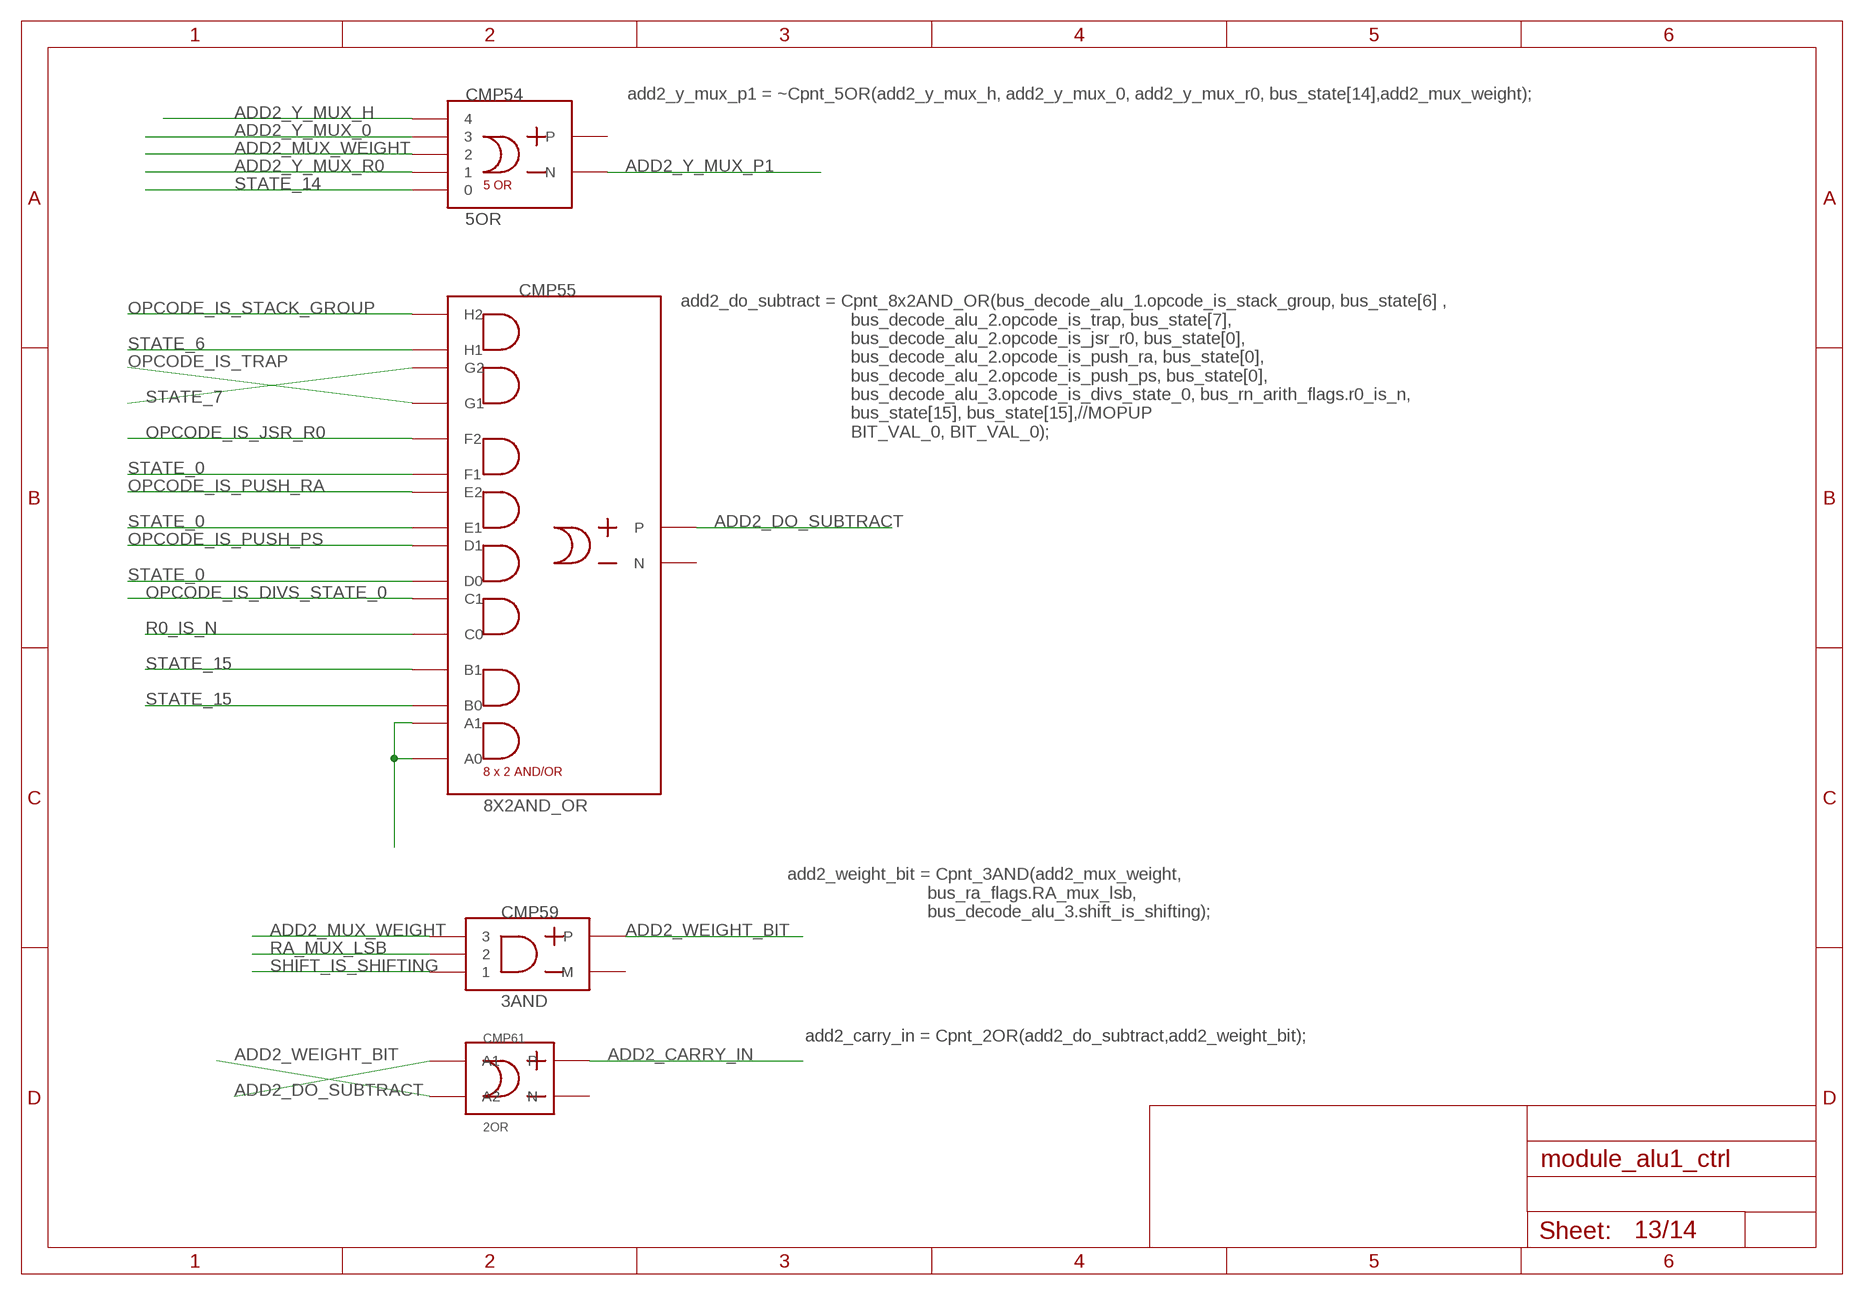
[diagram p12: schematic, sheet 13]
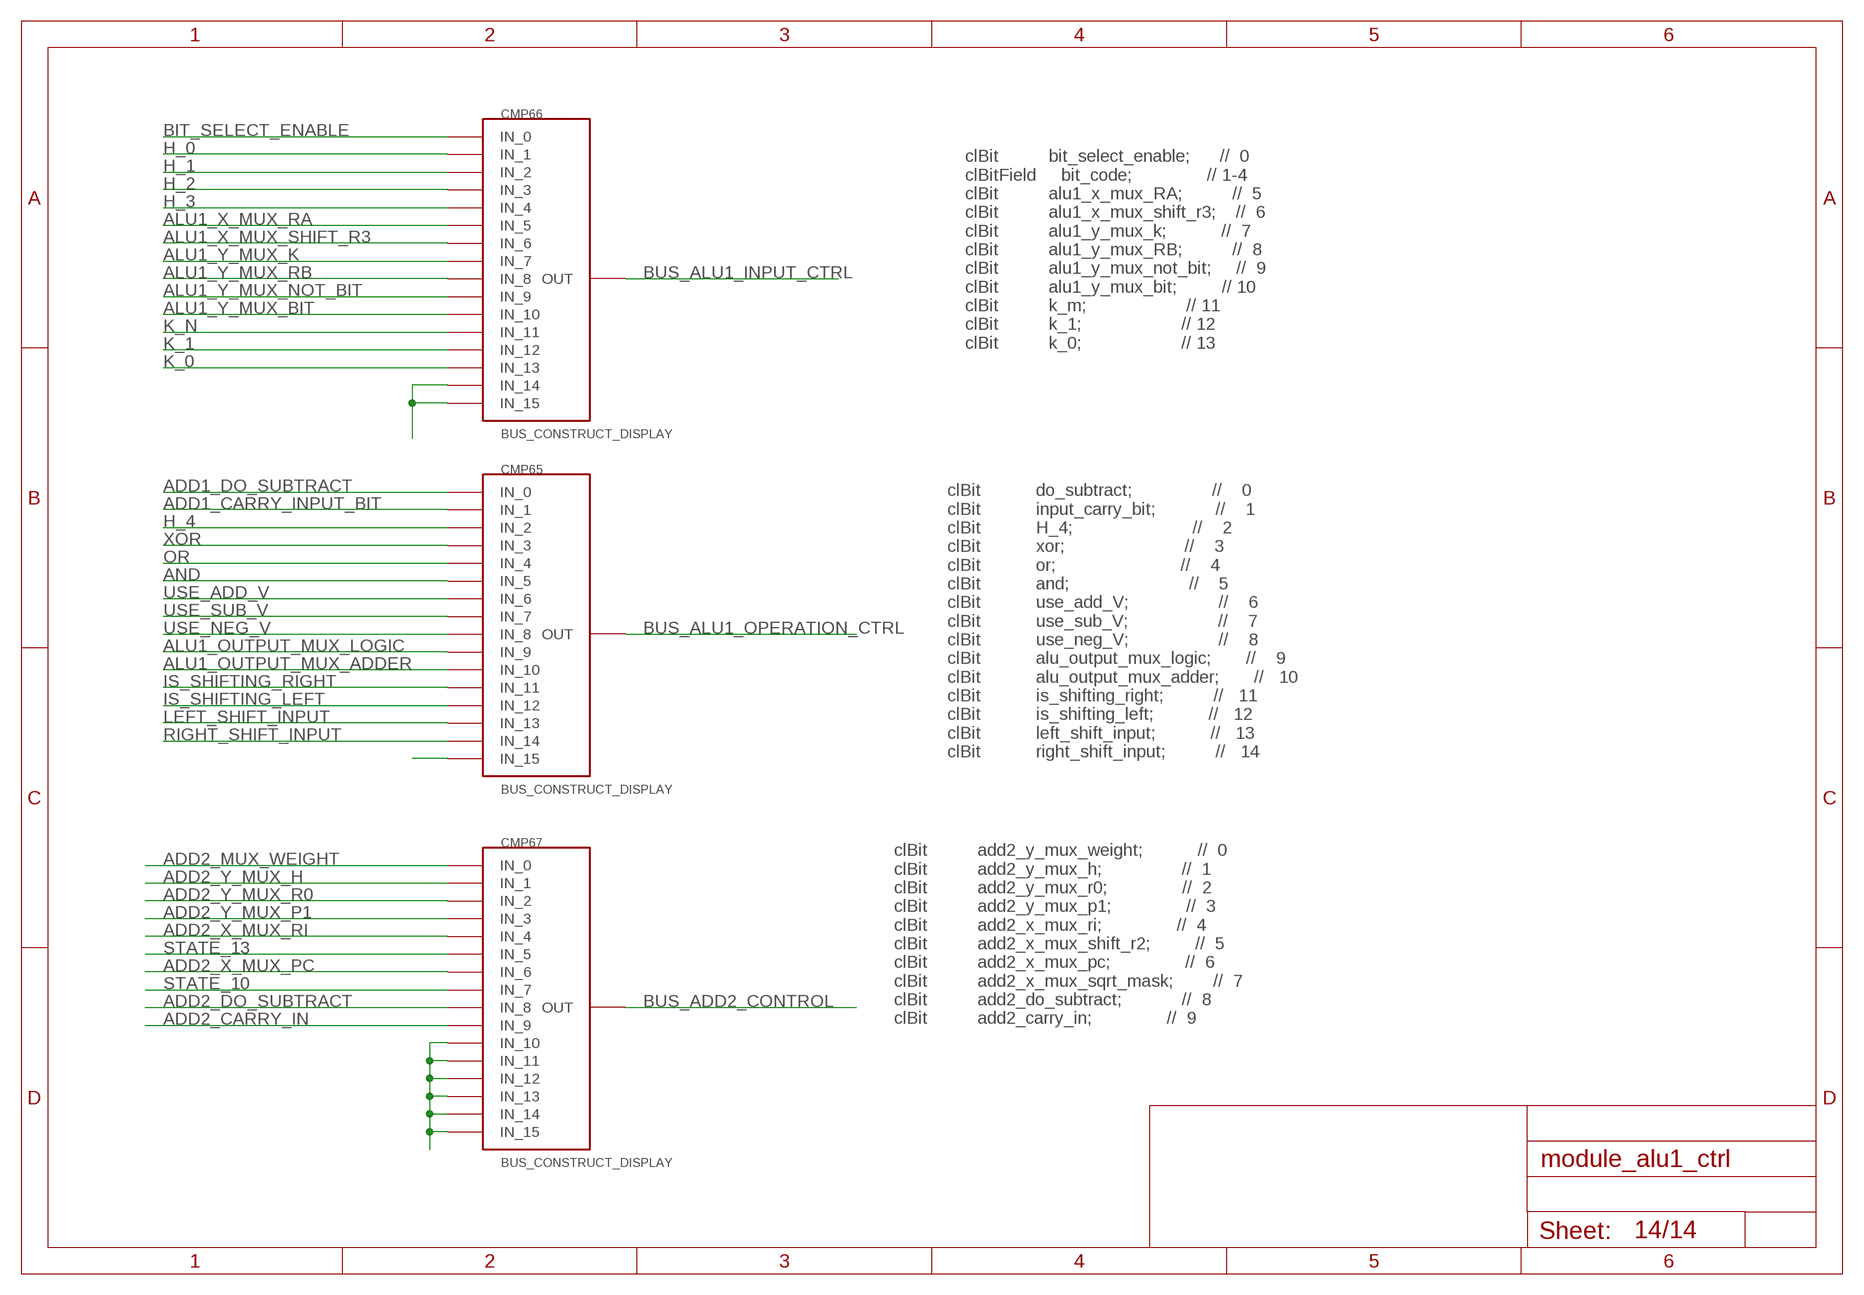
[diagram p13: schematic, sheet 14]

(export (version "E")
  (design (tool "Eeschema 10.0.6"))
  (components
    (comp (ref "CMP65")
      (value "BUS_CONSTRUCT_DISPLAY")
      (footprint "eagle-import:BUS_SPLIT_DISPLAY")
      (libsource (lib "eagle-import") (part "BUS_CONSTRUCT_DISPLAY"))
    )
    (comp (ref "CMP66")
      (value "BUS_CONSTRUCT_DISPLAY")
      (footprint "eagle-import:BUS_SPLIT_DISPLAY")
      (libsource (lib "eagle-import") (part "BUS_CONSTRUCT_DISPLAY"))
    )
    (comp (ref "CMP67")
      (value "BUS_CONSTRUCT_DISPLAY")
      (footprint "eagle-import:BUS_SPLIT_DISPLAY")
      (libsource (lib "eagle-import") (part "BUS_CONSTRUCT_DISPLAY"))
    )
    (comp (ref "CMP14")
      (value "2X2AND_OR")
      (footprint "eagle-import:2X2AND_OR")
      (libsource (lib "eagle-import") (part "2X2AND_OR"))
    )
    (comp (ref "CMP48")
      (value "2X2AND_OR")
      (footprint "eagle-import:2X2AND_OR")
      (libsource (lib "eagle-import") (part "2X2AND_OR"))
    )
    (comp (ref "CMP53")
      (value "4OR")
      (footprint "eagle-import:4OR")
      (libsource (lib "eagle-import") (part "4OR"))
    )
    (comp (ref "CMP56")
      (value "3AND")
      (footprint "eagle-import:3AND")
      (libsource (lib "eagle-import") (part "3AND"))
    )
    (comp (ref "CMP60")
      (value "5OR")
      (footprint "eagle-import:5OR")
      (libsource (lib "eagle-import") (part "5OR"))
    )
    (comp (ref "CMP62")
      (value "5OR")
      (footprint "eagle-import:5OR")
      (libsource (lib "eagle-import") (part "5OR"))
    )
    (comp (ref "CMP17")
      (value "3OR")
      (footprint "eagle-import:3OR")
      (libsource (lib "eagle-import") (part "3OR"))
    )
    (comp (ref "CMP47")
      (value "2AND")
      (footprint "eagle-import:2AND")
      (libsource (lib "eagle-import") (part "2AND"))
    )
    (comp (ref "CMP49")
      (value "4OR")
      (footprint "eagle-import:4OR")
      (libsource (lib "eagle-import") (part "4OR"))
    )
    (comp (ref "CMP50")
      (value "4OR")
      (footprint "eagle-import:4OR")
      (libsource (lib "eagle-import") (part "4OR"))
    )
    (comp (ref "CMP51")
      (value "2OR")
      (footprint "eagle-import:2OR")
      (libsource (lib "eagle-import") (part "2OR"))
    )
    (comp (ref "CMP52")
      (value "4X2AND_OR")
      (footprint "eagle-import:4X2AND_OR")
      (libsource (lib "eagle-import") (part "4X2AND_OR"))
    )
    (comp (ref "CMP3")
      (value "2AND")
      (footprint "eagle-import:2AND")
      (libsource (lib "eagle-import") (part "2AND"))
    )
    (comp (ref "CMP4")
      (value "2X2AND_OR")
      (footprint "eagle-import:2X2AND_OR")
      (libsource (lib "eagle-import") (part "2X2AND_OR"))
    )
    (comp (ref "CMP5")
      (value "8OR")
      (footprint "eagle-import:8OR")
      (libsource (lib "eagle-import") (part "8OR"))
    )
    (comp (ref "CMP6")
      (value "2OR")
      (footprint "eagle-import:2OR")
      (libsource (lib "eagle-import") (part "2OR"))
    )
    (comp (ref "CMP7")
      (value "4X2AND_OR")
      (footprint "eagle-import:4X2AND_OR")
      (libsource (lib "eagle-import") (part "4X2AND_OR"))
    )
    (comp (ref "CMP57")
      (value "1BUF")
      (footprint "eagle-import:1BUF")
      (libsource (lib "eagle-import") (part "1BUF"))
    )
    (comp (ref "CMP28")
      (value "2X2AND_OR")
      (footprint "eagle-import:2X2AND_OR")
      (libsource (lib "eagle-import") (part "2X2AND_OR"))
    )
    (comp (ref "CMP29")
      (value "8OR")
      (footprint "eagle-import:8OR")
      (libsource (lib "eagle-import") (part "8OR"))
    )
    (comp (ref "CMP30")
      (value "3OR")
      (footprint "eagle-import:3OR")
      (libsource (lib "eagle-import") (part "3OR"))
    )
    (comp (ref "CMP31")
      (value "4OR")
      (footprint "eagle-import:4OR")
      (libsource (lib "eagle-import") (part "4OR"))
    )
    (comp (ref "CMP32")
      (value "2AND")
      (footprint "eagle-import:2AND")
      (libsource (lib "eagle-import") (part "2AND"))
    )
    (comp (ref "CMP33")
      (value "2X2AND_OR")
      (footprint "eagle-import:2X2AND_OR")
      (libsource (lib "eagle-import") (part "2X2AND_OR"))
    )
    (comp (ref "CMP1")
      (value "BUS_SPLIT_DISPLAY")
      (footprint "eagle-import:BUS_SPLIT_DISPLAY")
      (libsource (lib "eagle-import") (part "BUS_SPLIT_DISPLAY"))
    )
    (comp (ref "CMP12")
      (value "BUS_SPLIT_DISPLAY")
      (footprint "eagle-import:BUS_SPLIT_DISPLAY")
      (libsource (lib "eagle-import") (part "BUS_SPLIT_DISPLAY"))
    )
    (comp (ref "CMP22")
      (value "BUS_SPLIT_DISPLAY")
      (footprint "eagle-import:BUS_SPLIT_DISPLAY")
      (libsource (lib "eagle-import") (part "BUS_SPLIT_DISPLAY"))
    )
    (comp (ref "CMP42")
      (value "2X2AND_OR")
      (footprint "eagle-import:2X2AND_OR")
      (libsource (lib "eagle-import") (part "2X2AND_OR"))
    )
    (comp (ref "CMP43")
      (value "2X2AND_OR")
      (footprint "eagle-import:2X2AND_OR")
      (libsource (lib "eagle-import") (part "2X2AND_OR"))
    )
    (comp (ref "CMP44")
      (value "2OR")
      (footprint "eagle-import:2OR")
      (libsource (lib "eagle-import") (part "2OR"))
    )
    (comp (ref "CMP45")
      (value "2X2AND_OR")
      (footprint "eagle-import:2X2AND_OR")
      (libsource (lib "eagle-import") (part "2X2AND_OR"))
    )
    (comp (ref "CMP46")
      (value "3OR")
      (footprint "eagle-import:3OR")
      (libsource (lib "eagle-import") (part "3OR"))
    )
    (comp (ref "CMP11")
      (value "2AND")
      (footprint "eagle-import:2AND")
      (libsource (lib "eagle-import") (part "2AND"))
    )
    (comp (ref "CMP16")
      (value "2AND")
      (footprint "eagle-import:2AND")
      (libsource (lib "eagle-import") (part "2AND"))
    )
    (comp (ref "CMP18")
      (value "2OR")
      (footprint "eagle-import:2OR")
      (libsource (lib "eagle-import") (part "2OR"))
    )
    (comp (ref "CMP19")
      (value "2AND")
      (footprint "eagle-import:2AND")
      (libsource (lib "eagle-import") (part "2AND"))
    )
    (comp (ref "CMP23")
      (value "2AND")
      (footprint "eagle-import:2AND")
      (libsource (lib "eagle-import") (part "2AND"))
    )
    (comp (ref "CMP34")
      (value "3OR")
      (footprint "eagle-import:3OR")
      (libsource (lib "eagle-import") (part "3OR"))
    )
    (comp (ref "CMP10")
      (value "DECODER4")
      (footprint "eagle-import:DECODER4")
      (libsource (lib "eagle-import") (part "DECODER4"))
    )
    (comp (ref "CMP20")
      (value "2AND")
      (footprint "eagle-import:2AND")
      (libsource (lib "eagle-import") (part "2AND"))
    )
    (comp (ref "CMP24")
      (value "2OR")
      (footprint "eagle-import:2OR")
      (libsource (lib "eagle-import") (part "2OR"))
    )
    (comp (ref "CMP26")
      (value "8OR")
      (footprint "eagle-import:8OR")
      (libsource (lib "eagle-import") (part "8OR"))
    )
    (comp (ref "CMP27")
      (value "2OR")
      (footprint "eagle-import:2OR")
      (libsource (lib "eagle-import") (part "2OR"))
    )
    (comp (ref "CMP41")
      (value "1BUF")
      (footprint "eagle-import:1BUF")
      (libsource (lib "eagle-import") (part "1BUF"))
    )
    (comp (ref "CMP54")
      (value "5OR")
      (footprint "eagle-import:5OR")
      (libsource (lib "eagle-import") (part "5OR"))
    )
    (comp (ref "CMP55")
      (value "8X2AND_OR")
      (footprint "eagle-import:8X2AND_OR")
      (libsource (lib "eagle-import") (part "8X2AND_OR"))
    )
    (comp (ref "CMP59")
      (value "3AND")
      (footprint "eagle-import:3AND")
      (libsource (lib "eagle-import") (part "3AND"))
    )
    (comp (ref "CMP61")
      (value "2OR")
      (footprint "eagle-import:2OR")
      (libsource (lib "eagle-import") (part "2OR"))
    )
    (comp (ref "CMP88")
      (value "BUS_SPLIT_DISPLAY")
      (footprint "eagle-import:BUS_SPLIT_DISPLAY")
      (libsource (lib "eagle-import") (part "BUS_SPLIT_DISPLAY"))
    )
    (comp (ref "CMP92")
      (value "BUS_SPLIT_DISPLAY")
      (footprint "eagle-import:BUS_SPLIT_DISPLAY")
      (libsource (lib "eagle-import") (part "BUS_SPLIT_DISPLAY"))
    )
    (comp (ref "CMP94")
      (value "BUS_SPLIT_DISPLAY")
      (footprint "eagle-import:BUS_SPLIT_DISPLAY")
      (libsource (lib "eagle-import") (part "BUS_SPLIT_DISPLAY"))
    )
    (comp (ref "CMP2")
      (value "3OR")
      (footprint "eagle-import:3OR")
      (libsource (lib "eagle-import") (part "3OR"))
    )
    (comp (ref "CMP8")
      (value "3OR")
      (footprint "eagle-import:3OR")
      (libsource (lib "eagle-import") (part "3OR"))
    )
    (comp (ref "CMP9")
      (value "2OR")
      (footprint "eagle-import:2OR")
      (libsource (lib "eagle-import") (part "2OR"))
    )
    (comp (ref "CMP25")
      (value "1BUF")
      (footprint "eagle-import:1BUF")
      (libsource (lib "eagle-import") (part "1BUF"))
    )
    (comp (ref "CMP36")
      (value "3AND")
      (footprint "eagle-import:3AND")
      (libsource (lib "eagle-import") (part "3AND"))
    )
    (comp (ref "CMP37")
      (value "3AND")
      (footprint "eagle-import:3AND")
      (libsource (lib "eagle-import") (part "3AND"))
    )
    (comp (ref "CMP38")
      (value "1BUF")
      (footprint "eagle-import:1BUF")
      (libsource (lib "eagle-import") (part "1BUF"))
    )
    (comp (ref "CMP35")
      (value "DECODER16")
      (footprint "eagle-import:DECODER16")
      (libsource (lib "eagle-import") (part "DECODER16"))
    )
    (comp (ref "CMP39")
      (value "BUS_CONSTRUCT_DISPLAY")
      (footprint "eagle-import:BUS_SPLIT_DISPLAY")
      (libsource (lib "eagle-import") (part "BUS_CONSTRUCT_DISPLAY"))
    )
    (comp (ref "CMP40")
      (value "BUS_2_BUS")
      (footprint "eagle-import:BUS2BUS")
      (libsource (lib "eagle-import") (part "BUS_2_BUS"))
    )
    (comp (ref "CMP13")
      (value "BUS_SPLIT_DISPLAY")
      (footprint "eagle-import:BUS_SPLIT_DISPLAY")
      (libsource (lib "eagle-import") (part "BUS_SPLIT_DISPLAY"))
    )
    (comp (ref "CMP15")
      (value "BUS_SPLIT_DISPLAY")
      (footprint "eagle-import:BUS_SPLIT_DISPLAY")
      (libsource (lib "eagle-import") (part "BUS_SPLIT_DISPLAY"))
    )
    (comp (ref "CMP21")
      (value "BUS_SPLIT_DISPLAY")
      (footprint "eagle-import:BUS_SPLIT_DISPLAY")
      (libsource (lib "eagle-import") (part "BUS_SPLIT_DISPLAY"))
    )
  )
  (nets
    (net (code "1") (name "ADD1_CARRY_INPUT_BIT") (class "Default")
      (node (ref "CMP65") (pin "P$2") (pinfunction "IN_1_P$2") (pintype "input"))
      (node (ref "CMP7") (pin "OUT_P") (pinfunction "P_OUT_P") (pintype "output"))
    )
    (net (code "2") (name "ADD1_DO_SUBTRACT") (class "Default")
      (node (ref "CMP5") (pin "OUT_P") (pinfunction "P_OUT_P") (pintype "output"))
      (node (ref "CMP65") (pin "P$1") (pinfunction "IN_0_P$1") (pintype "input"))
      (node (ref "CMP7") (pin "P$3") (pinfunction "B0_P$3") (pintype "input"))
    )
    (net (code "3") (name "ADD2_CARRY_IN") (class "Default")
      (node (ref "CMP61") (pin "OUT_P") (pinfunction "P_OUT_P") (pintype "output"))
      (node (ref "CMP67") (pin "P$10") (pinfunction "IN_9_P$10") (pintype "input"))
    )
    (net (code "4") (name "ADD2_DO_SUBTRACT") (class "Default")
      (node (ref "CMP55") (pin "OUT_P") (pinfunction "P_OUT_P") (pintype "output"))
      (node (ref "CMP61") (pin "P$2") (pinfunction "A1_P$2") (pintype "input"))
      (node (ref "CMP67") (pin "P$9") (pinfunction "IN_8_P$9") (pintype "input"))
    )
    (net (code "5") (name "ADD2_MUX_WEIGHT") (class "Default")
      (node (ref "CMP53") (pin "1") (pinfunction "0_1") (pintype "input"))
      (node (ref "CMP54") (pin "3") (pinfunction "2_3") (pintype "input"))
      (node (ref "CMP56") (pin "OUT_P") (pinfunction "P_OUT_P") (pintype "output"))
      (node (ref "CMP59") (pin "P$3") (pinfunction "3_P$3") (pintype "input"))
      (node (ref "CMP67") (pin "P$1") (pinfunction "IN_0_P$1") (pintype "input"))
    )
    (net (code "6") (name "ADD2_WEIGHT_BIT") (class "Default")
      (node (ref "CMP59") (pin "OUT_P") (pinfunction "P_OUT_P") (pintype "output"))
      (node (ref "CMP61") (pin "P$1") (pinfunction "A2_P$1") (pintype "input"))
    )
    (net (code "7") (name "ADD2_X_MUX_PC") (class "Default")
      (node (ref "CMP62") (pin "OUT_M") (pinfunction "N_OUT_M") (pintype "output"))
      (node (ref "CMP67") (pin "P$7") (pinfunction "IN_6_P$7") (pintype "input"))
    )
    (net (code "8") (name "ADD2_X_MUX_RI") (class "Default")
      (node (ref "CMP60") (pin "OUT_P") (pinfunction "P_OUT_P") (pintype "output"))
      (node (ref "CMP62") (pin "4") (pinfunction "3_4") (pintype "input"))
      (node (ref "CMP67") (pin "P$5") (pinfunction "IN_4_P$5") (pintype "input"))
    )
    (net (code "9") (name "ADD2_X_MUX_RI__H") (class "Default")
      (node (ref "CMP22") (pin "P$1") (pinfunction "OUT_0_P$1") (pintype "output"))
      (node (ref "CMP60") (pin "4") (pinfunction "3_4") (pintype "input"))
    )
    (net (code "10") (name "ADD2_X_MUX_RI__SET_A") (class "Default")
      (node (ref "CMP14") (pin "OUT_P") (pinfunction "P_OUT_P") (pintype "output"))
      (node (ref "CMP60") (pin "1") (pinfunction "0_1") (pintype "input"))
    )
    (net (code "11") (name "ADD2_X_MUX_RI__SP") (class "Default")
      (node (ref "CMP22") (pin "P$3") (pinfunction "OUT_2_P$3") (pintype "output"))
      (node (ref "CMP60") (pin "5") (pinfunction "4_5") (pintype "input"))
    )
    (net (code "12") (name "ADD2_X_MUX_RI__SP__JSR_ABS") (class "Default")
      (node (ref "CMP22") (pin "P$2") (pinfunction "OUT_1_P$2") (pintype "output"))
    )
    (net (code "13") (name "ADD2_X_ZERO") (class "Default")
      (node (ref "CMP53") (pin "OUT_P") (pinfunction "P_OUT_P") (pintype "output"))
      (node (ref "CMP62") (pin "3") (pinfunction "2_3") (pintype "input"))
    )
    (net (code "14") (name "ADD2_Y_MUX_0") (class "Default")
      (node (ref "CMP51") (pin "OUT_P") (pinfunction "P_OUT_P") (pintype "output"))
      (node (ref "CMP54") (pin "4") (pinfunction "3_4") (pintype "input"))
    )
    (net (code "15") (name "ADD2_Y_MUX_0__MUL") (class "Default")
      (node (ref "CMP17") (pin "OUT_M") (pinfunction "N_OUT_M") (pintype "output"))
      (node (ref "CMP51") (pin "P$2") (pinfunction "A1_P$2") (pintype "input"))
    )
    (net (code "16") (name "ADD2_Y_MUX_H") (class "Default")
      (node (ref "CMP49") (pin "OUT_P") (pinfunction "P_OUT_P") (pintype "output"))
      (node (ref "CMP54") (pin "5") (pinfunction "4_5") (pintype "input"))
      (node (ref "CMP67") (pin "P$2") (pinfunction "IN_1_P$2") (pintype "input"))
    )
    (net (code "17") (name "ADD2_Y_MUX_H__JSR") (class "Default")
      (node (ref "CMP47") (pin "OUT_P") (pinfunction "P_OUT_P") (pintype "output"))
      (node (ref "CMP49") (pin "1") (pinfunction "0_1") (pintype "input"))
    )
    (net (code "18") (name "ADD2_Y_MUX_P1") (class "Default")
      (node (ref "CMP54") (pin "OUT_M") (pinfunction "N_OUT_M") (pintype "output"))
      (node (ref "CMP67") (pin "P$4") (pinfunction "IN_3_P$4") (pintype "input"))
    )
    (net (code "19") (name "ADD2_Y_MUX_R0") (class "Default")
      (node (ref "CMP50") (pin "OUT_P") (pinfunction "P_OUT_P") (pintype "output"))
      (node (ref "CMP54") (pin "2") (pinfunction "1_2") (pintype "input"))
      (node (ref "CMP67") (pin "P$3") (pinfunction "IN_2_P$3") (pintype "input"))
    )
    (net (code "20") (name "ADD2_Y_MUX_R0__SET_A") (class "Default")
      (node (ref "CMP50") (pin "4") (pinfunction "3_4") (pintype "input"))
      (node (ref "CMP52") (pin "OUT_P") (pinfunction "P_OUT_P") (pintype "output"))
    )
    (net (code "21") (name "ADDER_X_SPECIAL") (class "Default")
      (node (ref "CMP22") (pin "P$5") (pinfunction "OUT_4_P$5") (pintype "output"))
      (node (ref "CMP28") (pin "P$2") (pinfunction "A1_P$2") (pintype "input"))
    )
    (net (code "22") (name "ADDER_Y_SPECIAL") (class "Default")
      (node (ref "CMP22") (pin "P$6") (pinfunction "OUT_5_P$6") (pintype "output"))
      (node (ref "CMP29") (pin "2") (pinfunction "1_2") (pintype "input"))
    )
    (net (code "23") (name "ALU1_OUTPUT_MUX_ADDER") (class "Default")
      (node (ref "CMP46") (pin "OUT_M") (pinfunction "N_OUT_M") (pintype "output"))
      (node (ref "CMP65") (pin "P$11") (pinfunction "IN_10_P$11") (pintype "input"))
    )
    (net (code "24") (name "ALU1_OUTPUT_MUX_LOGIC") (class "Default")
      (node (ref "CMP45") (pin "OUT_P") (pinfunction "P_OUT_P") (pintype "output"))
      (node (ref "CMP46") (pin "P$3") (pinfunction "2_P$3") (pintype "input"))
      (node (ref "CMP65") (pin "P$10") (pinfunction "IN_9_P$10") (pintype "input"))
    )
    (net (code "25") (name "ALU1_X_MUX_RA") (class "Default")
      (node (ref "CMP28") (pin "OUT_P") (pinfunction "P_OUT_P") (pintype "output"))
      (node (ref "CMP66") (pin "P$6") (pinfunction "IN_5_P$6") (pintype "input"))
    )
    (net (code "26") (name "ALU1_X_MUX_RA__SET_A") (class "Default")
      (node (ref "CMP26") (pin "OUT_P") (pinfunction "P_OUT_P") (pintype "output"))
      (node (ref "CMP28") (pin "P$4") (pinfunction "B1_P$4") (pintype "input"))
    )
    (net (code "27") (name "ALU1_X_MUX_SHIFT_R3") (class "Default")
      (node (ref "CMP27") (pin "OUT_P") (pinfunction "P_OUT_P") (pintype "output"))
      (node (ref "CMP66") (pin "P$7") (pinfunction "IN_6_P$7") (pintype "input"))
    )
    (net (code "28") (name "ALU1_X_MUX_SHIFT_R3_N") (class "Default")
      (node (ref "CMP27") (pin "OUT_M") (pinfunction "N_OUT_M") (pintype "output"))
      (node (ref "CMP28") (pin "P$1") (pinfunction "A0_P$1") (pintype "input"))
      (node (ref "CMP28") (pin "P$3") (pinfunction "B0_P$3") (pintype "input"))
    )
    (net (code "29") (name "ALU1_Y_MUX_BIT") (class "Default")
      (node (ref "CMP32") (pin "OUT_P") (pinfunction "P_OUT_P") (pintype "output"))
      (node (ref "CMP66") (pin "P$11") (pinfunction "IN_10_P$11") (pintype "input"))
    )
    (net (code "30") (name "ALU1_Y_MUX_K") (class "Default")
      (node (ref "CMP31") (pin "OUT_P") (pinfunction "P_OUT_P") (pintype "output"))
      (node (ref "CMP66") (pin "P$8") (pinfunction "IN_7_P$8") (pintype "input"))
    )
    (net (code "31") (name "ALU1_Y_MUX_NOT_BIT") (class "Default")
      (node (ref "CMP33") (pin "OUT_P") (pinfunction "P_OUT_P") (pintype "output"))
      (node (ref "CMP66") (pin "P$10") (pinfunction "IN_9_P$10") (pintype "input"))
    )
    (net (code "32") (name "ALU1_Y_MUX_RB") (class "Default")
      (node (ref "CMP30") (pin "OUT_P") (pinfunction "P_OUT_P") (pintype "output"))
      (node (ref "CMP66") (pin "P$9") (pinfunction "IN_8_P$9") (pintype "input"))
    )
    (net (code "33") (name "ALU1_Y_MUX_RB_A") (class "Default")
      (node (ref "CMP29") (pin "OUT_P") (pinfunction "P_OUT_P") (pintype "output"))
      (node (ref "CMP30") (pin "P$3") (pinfunction "2_P$3") (pintype "input"))
    )
    (net (code "34") (name "AND") (class "Default")
      (node (ref "CMP42") (pin "OUT_P") (pinfunction "P_OUT_P") (pintype "output"))
      (node (ref "CMP44") (pin "P$2") (pinfunction "A1_P$2") (pintype "input"))
      (node (ref "CMP65") (pin "P$6") (pinfunction "IN_5_P$6") (pintype "input"))
    )
    (net (code "35") (name "ARITH_RIGHT_INPUT") (class "Default")
      (node (ref "CMP19") (pin "OUT_P") (pinfunction "P_OUT_P") (pintype "output"))
      (node (ref "CMP34") (pin "P$1") (pinfunction "0_P$1") (pintype "input"))
    )
    (net (code "36") (name "BIT_SELECT_ENABLE") (class "Default")
      (node (ref "CMP41") (pin "N") (pinfunction "N_N") (pintype "output"))
      (node (ref "CMP66") (pin "P$1") (pinfunction "IN_0_P$1") (pintype "input"))
    )
    (net (code "37") (name "BIT_SHIFT_MODE_CHANGE__ARITH") (class "Default")
      (node (ref "CMP10") (pin "P1") (pinfunction "P1_P1") (pintype "output"))
      (node (ref "CMP19") (pin "P$1") (pinfunction "1_P$1") (pintype "input"))
    )
    (net (code "38") (name "BIT_SHIFT_MODE_CLEAR__ROTATE") (class "Default")
      (node (ref "CMP10") (pin "P2") (pinfunction "P2_P2") (pintype "output"))
      (node (ref "CMP16") (pin "P$1") (pinfunction "1_P$1") (pintype "input"))
      (node (ref "CMP23") (pin "P$1") (pinfunction "1_P$1") (pintype "input"))
      (node (ref "CMP33") (pin "P$3") (pinfunction "B0_P$3") (pintype "input"))
      (node (ref "CMP42") (pin "P$3") (pinfunction "B0_P$3") (pintype "input"))
    )
    (net (code "39") (name "BIT_SHIFT_MODE_CLEAR__ROTATE_N") (class "Default")
      (node (ref "CMP10") (pin "N2") (pinfunction "N2_N2") (pintype "output"))
      (node (ref "CMP32") (pin "P$1") (pinfunction "1_P$1") (pintype "input"))
    )
    (net (code "40") (name "BIT_SHIFT_MODE_SET__X_ROT") (class "Default")
      (node (ref "CMP10") (pin "P3") (pinfunction "P3_P3") (pintype "output"))
      (node (ref "CMP11") (pin "P$1") (pinfunction "1_P$1") (pintype "input"))
      (node (ref "CMP43") (pin "P$3") (pinfunction "B0_P$3") (pintype "input"))
    )
    (net (code "41") (name "BIT_SHIFT_MODE_TEST__LOGICAL") (class "Default")
      (node (ref "CMP10") (pin "P0") (pinfunction "P0_P0") (pintype "output"))
    )
    (net (code "42") (name "BIT_XX_ACTION_CYCLE") (class "Default")
      (node (ref "CMP24") (pin "OUT_M") (pinfunction "N_OUT_M") (pintype "output"))
      (node (ref "CMP26") (pin "3") (pinfunction "2_3") (pintype "input"))
      (node (ref "CMP32") (pin "P$2") (pinfunction "2_P$2") (pintype "input"))
      (node (ref "CMP33") (pin "P$4") (pinfunction "B1_P$4") (pintype "input"))
    )
    (net (code "43") (name "BIT_XX_LOAD_CYCLE") (class "Default")
      (node (ref "CMP20") (pin "OUT_P") (pinfunction "P_OUT_P") (pintype "output"))
      (node (ref "CMP30") (pin "P$1") (pinfunction "0_P$1") (pintype "input"))
    )
    (net (code "44") (name "BUS_ADD2_CONTROL") (class "Default")
      (node (ref "CMP67") (pin "INPUT") (pinfunction "OUT_INPUT") (pintype "output"))
    )
    (net (code "45") (name "BUS_ALU1_INPUT_CTRL") (class "Default")
      (node (ref "CMP66") (pin "INPUT") (pinfunction "OUT_INPUT") (pintype "output"))
    )
    (net (code "46") (name "BUS_ALU1_OPERATION_CTRL") (class "Default")
      (node (ref "CMP65") (pin "INPUT") (pinfunction "OUT_INPUT") (pintype "output"))
    )
    (net (code "47") (name "BUS_DECODE_ALU_1") (class "Default")
      (node (ref "CMP92") (pin "INPUT") (pinfunction "INPUT_INPUT") (pintype "input"))
    )
    (net (code "48") (name "BUS_DECODE_ALU_2") (class "Default")
      (node (ref "CMP88") (pin "INPUT") (pinfunction "INPUT_INPUT") (pintype "input"))
    )
    (net (code "49") (name "BUS_DECODE_ALU_3") (class "Default")
      (node (ref "CMP94") (pin "INPUT") (pinfunction "INPUT_INPUT") (pintype "input"))
    )
    (net (code "50") (name "BUS_H_D") (class "Default")
      (node (ref "CMP13") (pin "INPUT") (pinfunction "INPUT_INPUT") (pintype "input"))
    )
    (net (code "51") (name "BUS_PS") (class "Default")
      (node (ref "CMP21") (pin "INPUT") (pinfunction "INPUT_INPUT") (pintype "input"))
    )
    (net (code "52") (name "BUS_RA_FLAGS") (class "Default")
      (node (ref "CMP15") (pin "INPUT") (pinfunction "INPUT_INPUT") (pintype "input"))
    )
    (net (code "53") (name "BUS_RNX_SPECIALS") (class "Default")
      (node (ref "CMP22") (pin "INPUT") (pinfunction "INPUT_INPUT") (pintype "input"))
    )
    (net (code "54") (name "BUS_RN_ARITH_FLAGS") (class "Default")
      (node (ref "CMP1") (pin "INPUT") (pinfunction "INPUT_INPUT") (pintype "input"))
    )
    (net (code "55") (name "BUS_STATE") (class "Default")
      (node (ref "CMP12") (pin "INPUT") (pinfunction "INPUT_INPUT") (pintype "input"))
    )
    (net (code "56") (name "DO_SUBTRACT__SET_A") (class "Default")
      (node (ref "CMP4") (pin "OUT_P") (pinfunction "P_OUT_P") (pintype "output"))
      (node (ref "CMP5") (pin "7") (pinfunction "6_7") (pintype "input"))
    )
    (net (code "57") (name "FLAG_C") (class "Default")
      (node (ref "CMP21") (pin "P$6") (pinfunction "OUT_5_P$6") (pintype "output"))
    )
    (net (code "58") (name "FLAG_D") (class "Default")
      (node (ref "CMP21") (pin "P$7") (pinfunction "OUT_6_P$7") (pintype "output"))
    )
    (net (code "59") (name "FLAG_F0") (class "Default")
      (node (ref "CMP21") (pin "P$9") (pinfunction "OUT_8_P$9") (pintype "output"))
    )
    (net (code "60") (name "FLAG_F1") (class "Default")
      (node (ref "CMP21") (pin "P$10") (pinfunction "OUT_9_P$10") (pintype "output"))
    )
    (net (code "61") (name "FLAG_F2") (class "Default")
      (node (ref "CMP21") (pin "P$11") (pinfunction "OUT_10_P$11") (pintype "output"))
    )
    (net (code "62") (name "FLAG_F3") (class "Default")
      (node (ref "CMP21") (pin "P$12") (pinfunction "OUT_11_P$12") (pintype "output"))
      (node (ref "CMP31") (pin "1") (pinfunction "0_1") (pintype "input"))
    )
    (net (code "63") (name "FLAG_F4") (class "Default")
      (node (ref "CMP21") (pin "P$13") (pinfunction "OUT_12_P$13") (pintype "output"))
    )
    (net (code "64") (name "FLAG_F5") (class "Default")
      (node (ref "CMP21") (pin "P$14") (pinfunction "OUT_13_P$14") (pintype "output"))
    )
    (net (code "65") (name "FLAG_F6") (class "Default")
      (node (ref "CMP21") (pin "P$15") (pinfunction "OUT_14_P$15") (pintype "output"))
      (node (ref "CMP56") (pin "P$1") (pinfunction "1_P$1") (pintype "input"))
    )
    (net (code "66") (name "FLAG_I") (class "Default")
      (node (ref "CMP21") (pin "P$1") (pinfunction "OUT_0_P$1") (pintype "output"))
    )
    (net (code "67") (name "FLAG_N") (class "Default")
      (node (ref "CMP21") (pin "P$2") (pinfunction "OUT_1_P$2") (pintype "output"))
    )
    (net (code "68") (name "FLAG_V") (class "Default")
      (node (ref "CMP21") (pin "P$4") (pinfunction "OUT_3_P$4") (pintype "output"))
    )
    (net (code "69") (name "FLAG_X") (class "Default")
      (node (ref "CMP11") (pin "P$2") (pinfunction "2_P$2") (pintype "input"))
      (node (ref "CMP21") (pin "P$5") (pinfunction "OUT_4_P$5") (pintype "output"))
      (node (ref "CMP57") (pin "IN") (pinfunction "IN_IN") (pintype "input"))
      (node (ref "CMP7") (pin "P$7") (pinfunction "D0_P$7") (pintype "input"))
    )
    (net (code "70") (name "FLAG_X_N") (class "Default")
      (node (ref "CMP57") (pin "N") (pinfunction "N_N") (pintype "output"))
      (node (ref "CMP7") (pin "P$5") (pinfunction "C0_P$5") (pintype "input"))
    )
    (net (code "71") (name "FLAG_Z") (class "Default")
      (node (ref "CMP21") (pin "P$3") (pinfunction "OUT_2_P$3") (pintype "output"))
    )
    (net (code "72") (name "H_0") (class "Default")
      (node (ref "CMP13") (pin "P$1") (pinfunction "OUT_0_P$1") (pintype "output"))
      (node (ref "CMP66") (pin "P$2") (pinfunction "IN_1_P$2") (pintype "input"))
    )
    (net (code "73") (name "H_1") (class "Default")
      (node (ref "CMP13") (pin "P$2") (pinfunction "OUT_1_P$2") (pintype "output"))
      (node (ref "CMP35") (pin "A1") (pinfunction "A1_A1") (pintype "input"))
      (node (ref "CMP66") (pin "P$3") (pinfunction "IN_2_P$3") (pintype "input"))
    )
    (net (code "74") (name "H_2") (class "Default")
      (node (ref "CMP13") (pin "P$3") (pinfunction "OUT_2_P$3") (pintype "output"))
      (node (ref "CMP35") (pin "A2") (pinfunction "A2_A2") (pintype "input"))
      (node (ref "CMP66") (pin "P$4") (pinfunction "IN_3_P$4") (pintype "input"))
    )
    (net (code "75") (name "H_3") (class "Default")
      (node (ref "CMP13") (pin "P$4") (pinfunction "OUT_3_P$4") (pintype "output"))
      (node (ref "CMP35") (pin "A3") (pinfunction "A3_A3") (pintype "input"))
      (node (ref "CMP66") (pin "P$5") (pinfunction "IN_4_P$5") (pintype "input"))
    )
    (net (code "76") (name "H_4") (class "Default")
      (node (ref "CMP13") (pin "P$5") (pinfunction "OUT_4_P$5") (pintype "output"))
      (node (ref "CMP3") (pin "P$1") (pinfunction "1_P$1") (pintype "input"))
      (node (ref "CMP38") (pin "IN") (pinfunction "IN_IN") (pintype "input"))
      (node (ref "CMP65") (pin "P$3") (pinfunction "IN_2_P$3") (pintype "input"))
    )
    (net (code "77") (name "H_5") (class "Default")
      (node (ref "CMP13") (pin "P$6") (pinfunction "OUT_5_P$6") (pintype "output"))
    )
    (net (code "78") (name "H_6") (class "Default")
      (node (ref "CMP10") (pin "A0") (pinfunction "A0_A0") (pintype "input"))
      (node (ref "CMP13") (pin "P$7") (pinfunction "OUT_6_P$7") (pintype "output"))
    )
    (net (code "79") (name "H_7") (class "Default")
      (node (ref "CMP10") (pin "A1") (pinfunction "A1_A1") (pintype "input"))
      (node (ref "CMP13") (pin "P$8") (pinfunction "OUT_7_P$8") (pintype "output"))
    )
    (net (code "80") (name "H_8") (class "Default")
      (node (ref "CMP13") (pin "P$9") (pinfunction "OUT_8_P$9") (pintype "output"))
    )
    (net (code "81") (name "H_9") (class "Default")
      (node (ref "CMP13") (pin "P$10") (pinfunction "OUT_9_P$10") (pintype "output"))
    )
    (net (code "82") (name "H_10") (class "Default")
      (node (ref "CMP13") (pin "P$11") (pinfunction "OUT_10_P$11") (pintype "output"))
    )
    (net (code "83") (name "H_11") (class "Default")
      (node (ref "CMP13") (pin "P$12") (pinfunction "OUT_11_P$12") (pintype "output"))
    )
    (net (code "84") (name "H_12") (class "Default")
      (node (ref "CMP13") (pin "P$13") (pinfunction "OUT_12_P$13") (pintype "output"))
    )
    (net (code "85") (name "H_13") (class "Default")
      (node (ref "CMP13") (pin "P$14") (pinfunction "OUT_13_P$14") (pintype "output"))
    )
    (net (code "86") (name "H_14") (class "Default")
      (node (ref "CMP13") (pin "P$15") (pinfunction "OUT_14_P$15") (pintype "output"))
    )
    (net (code "87") (name "H_15") (class "Default")
      (node (ref "CMP13") (pin "P$16") (pinfunction "OUT_15_P$16") (pintype "output"))
    )
    (net (code "88") (name "IS_SHIFTING_LEFT") (class "Default")
      (node (ref "CMP36") (pin "OUT_P") (pinfunction "P_OUT_P") (pintype "output"))
      (node (ref "CMP46") (pin "P$2") (pinfunction "1_P$2") (pintype "input"))
      (node (ref "CMP65") (pin "P$13") (pinfunction "IN_12_P$13") (pintype "input"))
    )
    (net (code "89") (name "IS_SHIFTING_RIGHT") (class "Default")
      (node (ref "CMP37") (pin "OUT_P") (pinfunction "P_OUT_P") (pintype "output"))
      (node (ref "CMP46") (pin "P$1") (pinfunction "0_P$1") (pintype "input"))
      (node (ref "CMP65") (pin "P$12") (pinfunction "IN_11_P$12") (pintype "input"))
    )
    (net (code "90") (name "JMP_R0_MOVE_SP_R0_STATE_0") (class "Default")
      (node (ref "CMP48") (pin "OUT_P") (pinfunction "P_OUT_P") (pintype "output"))
      (node (ref "CMP50") (pin "3") (pinfunction "2_3") (pintype "input"))
      (node (ref "CMP53") (pin "4") (pinfunction "3_4") (pintype "input"))
    )
    (net (code "91") (name "K_0") (class "Default")
      (node (ref "CMP66") (pin "P$14") (pinfunction "IN_13_P$14") (pintype "input"))
      (node (ref "CMP94") (pin "P$7") (pinfunction "OUT_6_P$7") (pintype "output"))
    )
    (net (code "92") (name "K_1") (class "Default")
      (node (ref "CMP66") (pin "P$13") (pinfunction "IN_12_P$13") (pintype "input"))
      (node (ref "CMP94") (pin "P$8") (pinfunction "OUT_7_P$8") (pintype "output"))
    )
    (net (code "93") (name "K_N") (class "Default")
      (node (ref "CMP66") (pin "P$12") (pinfunction "IN_11_P$12") (pintype "input"))
      (node (ref "CMP94") (pin "P$9") (pinfunction "OUT_8_P$9") (pintype "output"))
    )
    (net (code "94") (name "LEFT_SHIFT_INPUT") (class "Default")
      (node (ref "CMP18") (pin "OUT_P") (pinfunction "P_OUT_P") (pintype "output"))
      (node (ref "CMP65") (pin "P$14") (pinfunction "IN_13_P$14") (pintype "input"))
    )
    (net (code "95") (name "N$7") (class "Default")
      (node (ref "CMP35") (pin "A0") (pinfunction "A0_A0") (pintype "input"))
    )
    (net (code "96") (name "NEGATE_FOR_SHIFT") (class "Default")
      (node (ref "CMP3") (pin "OUT_P") (pinfunction "P_OUT_P") (pintype "output"))
      (node (ref "CMP5") (pin "2") (pinfunction "1_2") (pintype "input"))
    )
    (net (code "97") (name "NEXT_ADDR_MUX_RI__SP") (class "Default")
      (node (ref "CMP22") (pin "P$4") (pinfunction "OUT_3_P$4") (pintype "output"))
    )
    (net (code "98") (name "Net-(CMP7-A0)") (class "Default")
      (node (ref "CMP7") (pin "P$1") (pinfunction "A0_P$1") (pintype "input"))
      (node (ref "CMP7") (pin "P$2") (pinfunction "A1_P$2") (pintype "input"))
    )
    (net (code "99") (name "Net-(CMP39-IN_0)") (class "Default")
      (node (ref "CMP35") (pin "P14") (pinfunction "P14_P14") (pintype "output"))
      (node (ref "CMP39") (pin "P$1") (pinfunction "IN_0_P$1") (pintype "input"))
    )
    (net (code "100") (name "Net-(CMP39-IN_1)") (class "Default")
      (node (ref "CMP35") (pin "P13") (pinfunction "P13_P13") (pintype "output"))
      (node (ref "CMP39") (pin "P$2") (pinfunction "IN_1_P$2") (pintype "input"))
    )
    (net (code "101") (name "Net-(CMP39-IN_2)") (class "Default")
      (node (ref "CMP35") (pin "P12") (pinfunction "P12_P12") (pintype "output"))
      (node (ref "CMP39") (pin "P$3") (pinfunction "IN_2_P$3") (pintype "input"))
    )
    (net (code "102") (name "Net-(CMP39-IN_3)") (class "Default")
      (node (ref "CMP35") (pin "P11") (pinfunction "P11_P11") (pintype "output"))
      (node (ref "CMP39") (pin "P$4") (pinfunction "IN_3_P$4") (pintype "input"))
    )
    (net (code "103") (name "Net-(CMP39-IN_4)") (class "Default")
      (node (ref "CMP35") (pin "P10") (pinfunction "P10_P10") (pintype "output"))
      (node (ref "CMP39") (pin "P$5") (pinfunction "IN_4_P$5") (pintype "input"))
    )
    (net (code "104") (name "Net-(CMP39-IN_5)") (class "Default")
      (node (ref "CMP35") (pin "P9") (pinfunction "P9_P9") (pintype "output"))
      (node (ref "CMP39") (pin "P$6") (pinfunction "IN_5_P$6") (pintype "input"))
    )
    (net (code "105") (name "Net-(CMP39-IN_6)") (class "Default")
      (node (ref "CMP35") (pin "P8") (pinfunction "P8_P8") (pintype "output"))
      (node (ref "CMP39") (pin "P$7") (pinfunction "IN_6_P$7") (pintype "input"))
    )
    (net (code "106") (name "Net-(CMP39-IN_7)") (class "Default")
      (node (ref "CMP35") (pin "P7") (pinfunction "P7_P7") (pintype "output"))
      (node (ref "CMP39") (pin "P$8") (pinfunction "IN_7_P$8") (pintype "input"))
    )
    (net (code "107") (name "Net-(CMP39-IN_8)") (class "Default")
      (node (ref "CMP35") (pin "P6") (pinfunction "P6_P6") (pintype "output"))
      (node (ref "CMP39") (pin "P$9") (pinfunction "IN_8_P$9") (pintype "input"))
    )
    (net (code "108") (name "Net-(CMP39-IN_9)") (class "Default")
      (node (ref "CMP35") (pin "P5") (pinfunction "P5_P5") (pintype "output"))
      (node (ref "CMP39") (pin "P$10") (pinfunction "IN_9_P$10") (pintype "input"))
    )
    (net (code "109") (name "Net-(CMP39-IN_10)") (class "Default")
      (node (ref "CMP35") (pin "P4") (pinfunction "P4_P4") (pintype "output"))
      (node (ref "CMP39") (pin "P$11") (pinfunction "IN_10_P$11") (pintype "input"))
    )
    (net (code "110") (name "Net-(CMP39-IN_11)") (class "Default")
      (node (ref "CMP35") (pin "P3") (pinfunction "P3_P3") (pintype "output"))
      (node (ref "CMP39") (pin "P$12") (pinfunction "IN_11_P$12") (pintype "input"))
    )
    (net (code "111") (name "Net-(CMP39-IN_12)") (class "Default")
      (node (ref "CMP35") (pin "P2") (pinfunction "P2_P2") (pintype "output"))
      (node (ref "CMP39") (pin "P$13") (pinfunction "IN_12_P$13") (pintype "input"))
    )
    (net (code "112") (name "Net-(CMP39-IN_13)") (class "Default")
      (node (ref "CMP35") (pin "P1") (pinfunction "P1_P1") (pintype "output"))
      (node (ref "CMP39") (pin "P$14") (pinfunction "IN_13_P$14") (pintype "input"))
    )
    (net (code "113") (name "Net-(CMP39-IN_14)") (class "Default")
      (node (ref "CMP35") (pin "P0") (pinfunction "P0_P0") (pintype "output"))
      (node (ref "CMP39") (pin "P$15") (pinfunction "IN_14_P$15") (pintype "input"))
    )
    (net (code "114") (name "Net-(CMP39-IN_15)") (class "Default")
      (node (ref "CMP35") (pin "P15") (pinfunction "P15_P15") (pintype "output"))
      (node (ref "CMP39") (pin "P$16") (pinfunction "IN_15_P$16") (pintype "input"))
    )
    (net (code "115") (name "Net-(CMP39-OUT)") (class "Default")
      (node (ref "CMP39") (pin "INPUT") (pinfunction "OUT_INPUT") (pintype "output"))
      (node (ref "CMP40") (pin "P$1") (pinfunction "IN_P$1") (pintype "input"))
    )
    (net (code "116") (name "Net-(CMP52-A0)") (class "Default")
      (node (ref "CMP52") (pin "P$1") (pinfunction "A0_P$1") (pintype "input"))
      (node (ref "CMP52") (pin "P$2") (pinfunction "A1_P$2") (pintype "input"))
    )
    (net (code "117") (name "Net-(CMP55-A0)") (class "Default")
      (node (ref "CMP55") (pin "P$1") (pinfunction "A0_P$1") (pintype "input"))
      (node (ref "CMP55") (pin "P$2") (pinfunction "A1_P$2") (pintype "input"))
    )
    (net (code "118") (name "Net-(CMP66-IN_14)") (class "Default")
      (node (ref "CMP66") (pin "P$15") (pinfunction "IN_14_P$15") (pintype "input"))
      (node (ref "CMP66") (pin "P$16") (pinfunction "IN_15_P$16") (pintype "input"))
    )
    (net (code "119") (name "Net-(CMP67-IN_10)") (class "Default")
      (node (ref "CMP67") (pin "P$11") (pinfunction "IN_10_P$11") (pintype "input"))
      (node (ref "CMP67") (pin "P$12") (pinfunction "IN_11_P$12") (pintype "input"))
      (node (ref "CMP67") (pin "P$13") (pinfunction "IN_12_P$13") (pintype "input"))
      (node (ref "CMP67") (pin "P$14") (pinfunction "IN_13_P$14") (pintype "input"))
      (node (ref "CMP67") (pin "P$15") (pinfunction "IN_14_P$15") (pintype "input"))
      (node (ref "CMP67") (pin "P$16") (pinfunction "IN_15_P$16") (pintype "input"))
    )
    (net (code "120") (name "OPCODE_IS_ABS") (class "Default")
      (node (ref "CMP4") (pin "P$4") (pinfunction "B1_P$4") (pintype "input"))
      (node (ref "CMP88") (pin "P$14") (pinfunction "OUT_13_P$14") (pintype "output"))
    )
    (net (code "121") (name "OPCODE_IS_ADDQ_GROUP") (class "Default")
      (node (ref "CMP2") (pin "P$2") (pinfunction "1_P$2") (pintype "input"))
      (node (ref "CMP26") (pin "6") (pinfunction "5_6") (pintype "input"))
      (node (ref "CMP31") (pin "2") (pinfunction "1_2") (pintype "input"))
      (node (ref "CMP94") (pin "P$6") (pinfunction "OUT_5_P$6") (pintype "output"))
    )
    (net (code "122") (name "OPCODE_IS_ADDX") (class "Default")
      (node (ref "CMP2") (pin "P$3") (pinfunction "2_P$3") (pintype "input"))
      (node (ref "CMP7") (pin "P$8") (pinfunction "D1_P$8") (pintype "input"))
      (node (ref "CMP88") (pin "P$12") (pinfunction "OUT_11_P$12") (pintype "output"))
    )
    (net (code "123") (name "OPCODE_IS_ADD_GROUP") (class "Default")
      (node (ref "CMP2") (pin "P$1") (pinfunction "0_P$1") (pintype "input"))
      (node (ref "CMP26") (pin "2") (pinfunction "1_2") (pintype "input"))
      (node (ref "CMP29") (pin "4") (pinfunction "3_4") (pintype "input"))
      (node (ref "CMP88") (pin "P$9") (pinfunction "OUT_8_P$9") (pintype "output"))
    )
    (net (code "124") (name "OPCODE_IS_ADD_SP_STATE_2") (class "Default")
      (node (ref "CMP49") (pin "2") (pinfunction "1_2") (pintype "input"))
      (node (ref "CMP92") (pin "P$15") (pinfunction "OUT_14_P$15") (pintype "output"))
    )
    (net (code "125") (name "OPCODE_IS_AND_GROUP") (class "Default")
      (node (ref "CMP26") (pin "1") (pinfunction "0_1") (pintype "input"))
      (node (ref "CMP29") (pin "8") (pinfunction "7_8") (pintype "input"))
      (node (ref "CMP42") (pin "P$1") (pinfunction "A0_P$1") (pintype "input"))
      (node (ref "CMP42") (pin "P$2") (pinfunction "A1_P$2") (pintype "input"))
      (node (ref "CMP88") (pin "P$8") (pinfunction "OUT_7_P$8") (pintype "output"))
    )
    (net (code "126") (name "OPCODE_IS_BIT_XX") (class "Default")
      (node (ref "CMP20") (pin "P$1") (pinfunction "1_P$1") (pintype "input"))
      (node (ref "CMP42") (pin "P$4") (pinfunction "B1_P$4") (pintype "input"))
      (node (ref "CMP43") (pin "P$4") (pinfunction "B1_P$4") (pintype "input"))
      (node (ref "CMP45") (pin "P$4") (pinfunction "B1_P$4") (pintype "input"))
      (node (ref "CMP88") (pin "P$5") (pinfunction "OUT_4_P$5") (pintype "output"))
    )
    (net (code "127") (name "OPCODE_IS_BIT_XX_N") (class "Default")
      (node (ref "CMP24") (pin "P$2") (pinfunction "A1_P$2") (pintype "input"))
      (node (ref "CMP94") (pin "P$2") (pinfunction "OUT_1_P$2") (pintype "output"))
    )
    (net (code "128") (name "OPCODE_IS_BXX_STATE_2") (class "Default")
      (node (ref "CMP49") (pin "4") (pinfunction "3_4") (pintype "input"))
      (node (ref "CMP88") (pin "P$1") (pinfunction "OUT_0_P$1") (pintype "output"))
    )
    (net (code "129") (name "OPCODE_IS_CMP") (class "Default")
      (node (ref "CMP26") (pin "5") (pinfunction "4_5") (pintype "input"))
      (node (ref "CMP5") (pin "3") (pinfunction "2_3") (pintype "input"))
      (node (ref "CMP8") (pin "P$3") (pinfunction "2_P$3") (pintype "input"))
      (node (ref "CMP94") (pin "P$1") (pinfunction "OUT_0_P$1") (pintype "output"))
    )
    (net (code "130") (name "OPCODE_IS_CMP_GROUP") (class "Default")
      (node (ref "CMP29") (pin "3") (pinfunction "2_3") (pintype "input"))
      (node (ref "CMP94") (pin "P$10") (pinfunction "OUT_9_P$10") (pintype "output"))
    )
    (net (code "131") (name "OPCODE_IS_DIV") (class "Default")
      (node (ref "CMP5") (pin "8") (pinfunction "7_8") (pintype "input"))
      (node (ref "CMP88") (pin "P$15") (pinfunction "OUT_14_P$15") (pintype "output"))
    )
    (net (code "132") (name "OPCODE_IS_DIVS_STATE_0") (class "Default")
      (node (ref "CMP55") (pin "P$6") (pinfunction "C1_P$6") (pintype "input"))
      (node (ref "CMP92") (pin "P$2") (pinfunction "OUT_1_P$2") (pintype "output"))
    )
    (net (code "133") (name "OPCODE_IS_DIV_STATE_0") (class "Default")
      (node (ref "CMP50") (pin "1") (pinfunction "0_1") (pintype "input"))
      (node (ref "CMP53") (pin "2") (pinfunction "1_2") (pintype "input"))
      (node (ref "CMP92") (pin "P$7") (pinfunction "OUT_6_P$7") (pintype "output"))
    )
    (net (code "134") (name "OPCODE_IS_INDIRECT_POSTINC") (class "Default")
      (node (ref "CMP14") (pin "P$3") (pinfunction "B0_P$3") (pintype "input"))
      (node (ref "CMP92") (pin "P$9") (pinfunction "OUT_8_P$9") (pintype "output"))
    )
    (net (code "135") (name "OPCODE_IS_INV") (class "Default")
      (node (ref "CMP33") (pin "P$1") (pinfunction "A0_P$1") (pintype "input"))
      (node (ref "CMP33") (pin "P$2") (pinfunction "A1_P$2") (pintype "input"))
      (node (ref "CMP41") (pin "IN") (pinfunction "IN_IN") (pintype "input"))
      (node (ref "CMP94") (pin "P$3") (pinfunction "OUT_2_P$3") (pintype "output"))
    )
    (net (code "136") (name "OPCODE_IS_JMP_R0") (class "Default")
      (node (ref "CMP48") (pin "P$3") (pinfunction "B0_P$3") (pintype "input"))
      (node (ref "CMP92") (pin "P$11") (pinfunction "OUT_10_P$11") (pintype "output"))
    )
    (net (code "137") (name "OPCODE_IS_JSR_ABS") (class "Default")
      (node (ref "CMP47") (pin "P$2") (pinfunction "2_P$2") (pintype "input"))
      (node (ref "CMP92") (pin "P$14") (pinfunction "OUT_13_P$14") (pintype "output"))
    )
    (net (code "138") (name "OPCODE_IS_JSR_R0") (class "Default")
      (node (ref "CMP52") (pin "P$6") (pinfunction "C1_P$6") (pintype "input"))
      (node (ref "CMP55") (pin "P$12") (pinfunction "F2_P$12") (pintype "input"))
      (node (ref "CMP92") (pin "P$5") (pinfunction "OUT_4_P$5") (pintype "output"))
    )
    (net (code "139") (name "OPCODE_IS_JSR_X_STATE_7") (class "Default")
      (node (ref "CMP53") (pin "3") (pinfunction "2_3") (pintype "input"))
      (node (ref "CMP92") (pin "P$8") (pinfunction "OUT_7_P$8") (pintype "output"))
    )
    (net (code "140") (name "OPCODE_IS_LOGIC_GROUP") (class "Default")
      (node (ref "CMP45") (pin "P$1") (pinfunction "A0_P$1") (pintype "input"))
      (node (ref "CMP45") (pin "P$2") (pinfunction "A1_P$2") (pintype "input"))
      (node (ref "CMP88") (pin "P$3") (pinfunction "OUT_2_P$3") (pintype "output"))
    )
    (net (code "141") (name "OPCODE_IS_MOVER") (class "Default")
      (node (ref "CMP29") (pin "5") (pinfunction "4_5") (pintype "input"))
      (node (ref "CMP94") (pin "P$11") (pinfunction "OUT_10_P$11") (pintype "output"))
    )
    (net (code "142") (name "OPCODE_IS_MOVE_R0_SP_STATE_0") (class "Default")
      (node (ref "CMP51") (pin "P$1") (pinfunction "A2_P$1") (pintype "input"))
      (node (ref "CMP92") (pin "P$12") (pinfunction "OUT_11_P$12") (pintype "output"))
    )
    (net (code "143") (name "OPCODE_IS_MOVE_SP_R0") (class "Default")
      (node (ref "CMP48") (pin "P$1") (pinfunction "A0_P$1") (pintype "input"))
      (node (ref "CMP92") (pin "P$10") (pinfunction "OUT_9_P$10") (pintype "output"))
    )
    (net (code "144") (name "OPCODE_IS_MULS") (class "Default")
      (node (ref "CMP4") (pin "P$2") (pinfunction "A1_P$2") (pintype "input"))
      (node (ref "CMP88") (pin "P$13") (pinfunction "OUT_12_P$13") (pintype "output"))
    )
    (net (code "145") (name "OPCODE_IS_MUL_N") (class "Default")
      (node (ref "CMP17") (pin "P$2") (pinfunction "1_P$2") (pintype "input"))
      (node (ref "CMP92") (pin "P$13") (pinfunction "OUT_12_P$13") (pintype "output"))
    )
    (net (code "146") (name "OPCODE_IS_NEG") (class "Default")
      (node (ref "CMP88") (pin "P$4") (pinfunction "OUT_3_P$4") (pintype "output"))
      (node (ref "CMP9") (pin "P$1") (pinfunction "A2_P$1") (pintype "input"))
    )
    (net (code "147") (name "OPCODE_IS_NEGX") (class "Default")
      (node (ref "CMP5") (pin "5") (pinfunction "4_5") (pintype "input"))
      (node (ref "CMP6") (pin "P$1") (pinfunction "A2_P$1") (pintype "input"))
      (node (ref "CMP88") (pin "P$10") (pinfunction "OUT_9_P$10") (pintype "output"))
      (node (ref "CMP9") (pin "P$2") (pinfunction "A1_P$2") (pintype "input"))
    )
    (net (code "148") (name "OPCODE_IS_OR") (class "Default")
      (node (ref "CMP29") (pin "7") (pinfunction "6_7") (pintype "input"))
      (node (ref "CMP43") (pin "P$1") (pinfunction "A0_P$1") (pintype "input"))
      (node (ref "CMP43") (pin "P$2") (pinfunction "A1_P$2") (pintype "input"))
      (node (ref "CMP88") (pin "P$7") (pinfunction "OUT_6_P$7") (pintype "output"))
    )
    (net (code "149") (name "OPCODE_IS_OR_GROUP") (class "Default")
      (node (ref "CMP26") (pin "8") (pinfunction "7_8") (pintype "input"))
      (node (ref "CMP94") (pin "P$12") (pinfunction "OUT_11_P$12") (pintype "output"))
    )
    (net (code "150") (name "OPCODE_IS_PUSH_PS") (class "Default")
      (node (ref "CMP55") (pin "P$8") (pinfunction "D1_P$8") (pintype "input"))
      (node (ref "CMP92") (pin "P$3") (pinfunction "OUT_2_P$3") (pintype "output"))
    )
    (net (code "151") (name "OPCODE_IS_PUSH_RA") (class "Default")
      (node (ref "CMP55") (pin "P$10") (pinfunction "E2_P$10") (pintype "input"))
      (node (ref "CMP92") (pin "P$4") (pinfunction "OUT_3_P$4") (pintype "output"))
    )
    (net (code "152") (name "OPCODE_IS_SHIFT_XX") (class "Default")
      (node (ref "CMP3") (pin "P$2") (pinfunction "2_P$2") (pintype "input"))
      (node (ref "CMP30") (pin "P$2") (pinfunction "1_P$2") (pintype "input"))
      (node (ref "CMP36") (pin "P$3") (pinfunction "3_P$3") (pintype "input"))
      (node (ref "CMP37") (pin "P$3") (pinfunction "3_P$3") (pintype "input"))
      (node (ref "CMP56") (pin "P$2") (pinfunction "2_P$2") (pintype "input"))
      (node (ref "CMP88") (pin "P$2") (pinfunction "OUT_1_P$2") (pintype "output"))
    )
    (net (code "153") (name "OPCODE_IS_SQRT") (class "Default")
      (node (ref "CMP5") (pin "1") (pinfunction "0_1") (pintype "input"))
      (node (ref "CMP88") (pin "P$16") (pinfunction "OUT_15_P$16") (pintype "output"))
    )
    (net (code "154") (name "OPCODE_IS_STACK_GROUP") (class "Default")
      (node (ref "CMP31") (pin "3") (pinfunction "2_3") (pintype "input"))
      (node (ref "CMP55") (pin "P$16") (pinfunction "H2_P$16") (pintype "input"))
      (node (ref "CMP94") (pin "P$5") (pinfunction "OUT_4_P$5") (pintype "output"))
    )
    (net (code "155") (name "OPCODE_IS_STACK_REL_STATE_2") (class "Default")
      (node (ref "CMP49") (pin "3") (pinfunction "2_3") (pintype "input"))
      (node (ref "CMP92") (pin "P$16") (pinfunction "OUT_15_P$16") (pintype "output"))
    )
    (net (code "156") (name "OPCODE_IS_SUB") (class "Default")
      (node (ref "CMP26") (pin "7") (pinfunction "6_7") (pintype "input"))
      (node (ref "CMP8") (pin "P$1") (pinfunction "0_P$1") (pintype "input"))
      (node (ref "CMP88") (pin "P$6") (pinfunction "OUT_5_P$6") (pintype "output"))
    )
    (net (code "157") (name "OPCODE_IS_SUBX") (class "Default")
      (node (ref "CMP5") (pin "4") (pinfunction "3_4") (pintype "input"))
      (node (ref "CMP6") (pin "P$2") (pinfunction "A1_P$2") (pintype "input"))
      (node (ref "CMP8") (pin "P$2") (pinfunction "1_P$2") (pintype "input"))
      (node (ref "CMP88") (pin "P$11") (pinfunction "OUT_10_P$11") (pintype "output"))
    )
    (net (code "158") (name "OPCODE_IS_SUBX_NEGX") (class "Default")
      (node (ref "CMP6") (pin "OUT_P") (pinfunction "P_OUT_P") (pintype "output"))
      (node (ref "CMP7") (pin "P$6") (pinfunction "C1_P$6") (pintype "input"))
    )
    (net (code "159") (name "OPCODE_IS_SUBX_NEGX_N") (class "Default")
      (node (ref "CMP6") (pin "OUT_M") (pinfunction "N_OUT_M") (pintype "output"))
      (node (ref "CMP7") (pin "P$4") (pinfunction "B1_P$4") (pintype "input"))
    )
    (net (code "160") (name "OPCODE_IS_SUB_GROUP") (class "Default")
      (node (ref "CMP29") (pin "1") (pinfunction "0_1") (pintype "input"))
      (node (ref "CMP5") (pin "6") (pinfunction "5_6") (pintype "input"))
      (node (ref "CMP94") (pin "P$4") (pinfunction "OUT_3_P$4") (pintype "output"))
    )
    (net (code "161") (name "OPCODE_IS_TRAP") (class "Default")
      (node (ref "CMP55") (pin "P$13") (pinfunction "G1_P$13") (pintype "input"))
      (node (ref "CMP92") (pin "P$6") (pinfunction "OUT_5_P$6") (pintype "output"))
    )
    (net (code "162") (name "OPCODE_IS_XOR_GROUP") (class "Default")
      (node (ref "CMP26") (pin "4") (pinfunction "3_4") (pintype "input"))
      (node (ref "CMP29") (pin "6") (pinfunction "5_6") (pintype "input"))
      (node (ref "CMP94") (pin "P$13") (pinfunction "OUT_12_P$13") (pintype "output"))
    )
    (net (code "163") (name "OR") (class "Default")
      (node (ref "CMP43") (pin "OUT_P") (pinfunction "P_OUT_P") (pintype "output"))
      (node (ref "CMP44") (pin "P$1") (pinfunction "A2_P$1") (pintype "input"))
      (node (ref "CMP65") (pin "P$5") (pinfunction "IN_4_P$5") (pintype "input"))
    )
    (net (code "164") (name "R0_IS_N") (class "Default")
      (node (ref "CMP1") (pin "P$1") (pinfunction "OUT_0_P$1") (pintype "output"))
      (node (ref "CMP14") (pin "P$1") (pinfunction "A0_P$1") (pintype "input"))
      (node (ref "CMP55") (pin "P$5") (pinfunction "C0_P$5") (pintype "input"))
    )
    (net (code "165") (name "R0_IS_Z") (class "Default")
      (node (ref "CMP1") (pin "P$5") (pinfunction "OUT_4_P$5") (pintype "output"))
    )
    (net (code "166") (name "R1_IS_N") (class "Default")
      (node (ref "CMP1") (pin "P$2") (pinfunction "OUT_1_P$2") (pintype "output"))
      (node (ref "CMP17") (pin "P$1") (pinfunction "0_P$1") (pintype "input"))
      (node (ref "CMP52") (pin "P$3") (pinfunction "B0_P$3") (pintype "input"))
      (node (ref "CMP52") (pin "P$7") (pinfunction "D0_P$7") (pintype "input"))
    )
    (net (code "167") (name "R1_IS_Z") (class "Default")
      (node (ref "CMP1") (pin "P$6") (pinfunction "OUT_5_P$6") (pintype "output"))
    )
    (net (code "168") (name "R2_IS_N") (class "Default")
      (node (ref "CMP1") (pin "P$3") (pinfunction "OUT_2_P$3") (pintype "output"))
    )
    (net (code "169") (name "R2_IS_Z") (class "Default")
      (node (ref "CMP1") (pin "P$7") (pinfunction "OUT_6_P$7") (pintype "output"))
    )
    (net (code "170") (name "R3_IS_N") (class "Default")
      (node (ref "CMP1") (pin "P$4") (pinfunction "OUT_3_P$4") (pintype "output"))
    )
    (net (code "171") (name "R3_IS_Z") (class "Default")
      (node (ref "CMP1") (pin "P$8") (pinfunction "OUT_7_P$8") (pintype "output"))
    )
    (net (code "172") (name "RA_MUX_IS_N") (class "Default")
      (node (ref "CMP15") (pin "P$1") (pinfunction "OUT_0_P$1") (pintype "output"))
      (node (ref "CMP16") (pin "P$2") (pinfunction "2_P$2") (pintype "input"))
      (node (ref "CMP19") (pin "P$2") (pinfunction "2_P$2") (pintype "input"))
      (node (ref "CMP4") (pin "P$3") (pinfunction "B0_P$3") (pintype "input"))
    )
    (net (code "173") (name "RA_MUX_IS_Z") (class "Default")
      (node (ref "CMP15") (pin "P$2") (pinfunction "OUT_1_P$2") (pintype "output"))
    )
    (net (code "174") (name "RA_MUX_LSB") (class "Default")
      (node (ref "CMP15") (pin "P$3") (pinfunction "OUT_2_P$3") (pintype "output"))
      (node (ref "CMP23") (pin "P$2") (pinfunction "2_P$2") (pintype "input"))
      (node (ref "CMP59") (pin "P$2") (pinfunction "2_P$2") (pintype "input"))
    )
    (net (code "175") (name "RIGHT_SHIFT_INPUT") (class "Default")
      (node (ref "CMP34") (pin "OUT_P") (pinfunction "P_OUT_P") (pintype "output"))
      (node (ref "CMP65") (pin "P$15") (pinfunction "IN_14_P$15") (pintype "input"))
    )
    (net (code "176") (name "ROT_LEFT_INPUT") (class "Default")
      (node (ref "CMP16") (pin "OUT_P") (pinfunction "P_OUT_P") (pintype "output"))
      (node (ref "CMP18") (pin "P$2") (pinfunction "A1_P$2") (pintype "input"))
    )
    (net (code "177") (name "ROT_RIGHT_INPUT") (class "Default")
      (node (ref "CMP23") (pin "OUT_P") (pinfunction "P_OUT_P") (pintype "output"))
      (node (ref "CMP34") (pin "P$3") (pinfunction "2_P$3") (pintype "input"))
    )
    (net (code "178") (name "SHIFT_IS_SHIFTING") (class "Default")
      (node (ref "CMP59") (pin "P$1") (pinfunction "1_P$1") (pintype "input"))
      (node (ref "CMP92") (pin "P$1") (pinfunction "OUT_0_P$1") (pintype "output"))
    )
    (net (code "179") (name "SHIFT_LEFT") (class "Default")
      (node (ref "CMP36") (pin "P$1") (pinfunction "1_P$1") (pintype "input"))
      (node (ref "CMP38") (pin "N") (pinfunction "N_N") (pintype "output"))
    )
    (net (code "180") (name "SHIFT_RIGHT") (class "Default")
      (node (ref "CMP37") (pin "P$2") (pinfunction "2_P$2") (pintype "input"))
      (node (ref "CMP38") (pin "P") (pinfunction "P_P") (pintype "output"))
    )
    (net (code "181") (name "STATE_0") (class "Default")
      (node (ref "CMP12") (pin "P$1") (pinfunction "OUT_0_P$1") (pintype "output"))
      (node (ref "CMP14") (pin "P$4") (pinfunction "B1_P$4") (pintype "input"))
      (node (ref "CMP48") (pin "P$2") (pinfunction "A1_P$2") (pintype "input"))
      (node (ref "CMP48") (pin "P$4") (pinfunction "B1_P$4") (pintype "input"))
      (node (ref "CMP55") (pin "P$11") (pinfunction "F1_P$11") (pintype "input"))
      (node (ref "CMP55") (pin "P$7") (pinfunction "D0_P$7") (pintype "input"))
      (node (ref "CMP55") (pin "P$9") (pinfunction "E1_P$9") (pintype "input"))
    )
    (net (code "182") (name "STATE_1") (class "Default")
      (node (ref "CMP12") (pin "P$2") (pinfunction "OUT_1_P$2") (pintype "output"))
      (node (ref "CMP20") (pin "P$2") (pinfunction "2_P$2") (pintype "input"))
      (node (ref "CMP24") (pin "P$1") (pinfunction "A2_P$1") (pintype "input"))
      (node (ref "CMP25") (pin "IN") (pinfunction "IN_IN") (pintype "input"))
    )
    (net (code "183") (name "STATE_1_N") (class "Default")
      (node (ref "CMP25") (pin "N") (pinfunction "N_N") (pintype "output"))
      (node (ref "CMP36") (pin "P$2") (pinfunction "2_P$2") (pintype "input"))
      (node (ref "CMP37") (pin "P$1") (pinfunction "1_P$1") (pintype "input"))
      (node (ref "CMP45") (pin "P$3") (pinfunction "B0_P$3") (pintype "input"))
    )
    (net (code "184") (name "STATE_2") (class "Default")
      (node (ref "CMP12") (pin "P$3") (pinfunction "OUT_2_P$3") (pintype "output"))
      (node (ref "CMP56") (pin "P$3") (pinfunction "3_P$3") (pintype "input"))
    )
    (net (code "185") (name "STATE_3") (class "Default")
      (node (ref "CMP12") (pin "P$4") (pinfunction "OUT_3_P$4") (pintype "output"))
      (node (ref "CMP17") (pin "P$3") (pinfunction "2_P$3") (pintype "input"))
      (node (ref "CMP4") (pin "P$1") (pinfunction "A0_P$1") (pintype "input"))
    )
    (net (code "186") (name "STATE_4") (class "Default")
      (node (ref "CMP12") (pin "P$5") (pinfunction "OUT_4_P$5") (pintype "output"))
    )
    (net (code "187") (name "STATE_5") (class "Default")
      (node (ref "CMP12") (pin "P$6") (pinfunction "OUT_5_P$6") (pintype "output"))
    )
    (net (code "188") (name "STATE_6") (class "Default")
      (node (ref "CMP12") (pin "P$7") (pinfunction "OUT_6_P$7") (pintype "output"))
      (node (ref "CMP55") (pin "P$15") (pinfunction "H1_P$15") (pintype "input"))
    )
    (net (code "189") (name "STATE_7") (class "Default")
      (node (ref "CMP12") (pin "P$8") (pinfunction "OUT_7_P$8") (pintype "output"))
      (node (ref "CMP47") (pin "P$1") (pinfunction "1_P$1") (pintype "input"))
      (node (ref "CMP52") (pin "P$5") (pinfunction "C0_P$5") (pintype "input"))
      (node (ref "CMP55") (pin "P$14") (pinfunction "G2_P$14") (pintype "input"))
    )
    (net (code "190") (name "STATE_8") (class "Default")
      (node (ref "CMP12") (pin "P$9") (pinfunction "OUT_8_P$9") (pintype "output"))
    )
    (net (code "191") (name "STATE_9") (class "Default")
      (node (ref "CMP12") (pin "P$10") (pinfunction "OUT_9_P$10") (pintype "output"))
    )
    (net (code "192") (name "STATE_10") (class "Default")
      (node (ref "CMP12") (pin "P$11") (pinfunction "OUT_10_P$11") (pintype "output"))
      (node (ref "CMP50") (pin "2") (pinfunction "1_2") (pintype "input"))
      (node (ref "CMP62") (pin "1") (pinfunction "0_1") (pintype "input"))
      (node (ref "CMP67") (pin "P$8") (pinfunction "IN_7_P$8") (pintype "input"))
    )
    (net (code "193") (name "STATE_11") (class "Default")
      (node (ref "CMP12") (pin "P$12") (pinfunction "OUT_11_P$12") (pintype "output"))
      (node (ref "CMP27") (pin "P$1") (pinfunction "A2_P$1") (pintype "input"))
      (node (ref "CMP60") (pin "3") (pinfunction "2_3") (pintype "input"))
    )
    (net (code "194") (name "STATE_12") (class "Default")
      (node (ref "CMP12") (pin "P$13") (pinfunction "OUT_12_P$13") (pintype "output"))
      (node (ref "CMP60") (pin "2") (pinfunction "1_2") (pintype "input"))
    )
    (net (code "195") (name "STATE_13") (class "Default")
      (node (ref "CMP12") (pin "P$14") (pinfunction "OUT_13_P$14") (pintype "output"))
      (node (ref "CMP27") (pin "P$2") (pinfunction "A1_P$2") (pintype "input"))
      (node (ref "CMP31") (pin "4") (pinfunction "3_4") (pintype "input"))
      (node (ref "CMP52") (pin "P$8") (pinfunction "D1_P$8") (pintype "input"))
      (node (ref "CMP62") (pin "5") (pinfunction "4_5") (pintype "input"))
      (node (ref "CMP67") (pin "P$6") (pinfunction "IN_5_P$6") (pintype "input"))
    )
    (net (code "196") (name "STATE_14") (class "Default")
      (node (ref "CMP12") (pin "P$15") (pinfunction "OUT_14_P$15") (pintype "output"))
      (node (ref "CMP14") (pin "P$2") (pinfunction "A1_P$2") (pintype "input"))
      (node (ref "CMP52") (pin "P$4") (pinfunction "B1_P$4") (pintype "input"))
      (node (ref "CMP54") (pin "1") (pinfunction "0_1") (pintype "input"))
      (node (ref "CMP62") (pin "2") (pinfunction "1_2") (pintype "input"))
    )
    (net (code "197") (name "STATE_15") (class "Default")
      (node (ref "CMP12") (pin "P$16") (pinfunction "OUT_15_P$16") (pintype "output"))
      (node (ref "CMP55") (pin "P$3") (pinfunction "B0_P$3") (pintype "input"))
      (node (ref "CMP55") (pin "P$4") (pinfunction "B1_P$4") (pintype "input"))
    )
    (net (code "198") (name "USE_ADD_V") (class "Default")
      (node (ref "CMP2") (pin "OUT_P") (pinfunction "P_OUT_P") (pintype "output"))
      (node (ref "CMP65") (pin "P$7") (pinfunction "IN_6_P$7") (pintype "input"))
    )
    (net (code "199") (name "USE_NEG_V") (class "Default")
      (node (ref "CMP65") (pin "P$9") (pinfunction "IN_8_P$9") (pintype "input"))
      (node (ref "CMP9") (pin "OUT_P") (pinfunction "P_OUT_P") (pintype "output"))
    )
    (net (code "200") (name "USE_SUB_V") (class "Default")
      (node (ref "CMP65") (pin "P$8") (pinfunction "IN_7_P$8") (pintype "input"))
      (node (ref "CMP8") (pin "OUT_P") (pinfunction "P_OUT_P") (pintype "output"))
    )
    (net (code "201") (name "XOR") (class "Default")
      (node (ref "CMP44") (pin "OUT_M") (pinfunction "N_OUT_M") (pintype "output"))
      (node (ref "CMP65") (pin "P$4") (pinfunction "IN_3_P$4") (pintype "input"))
    )
    (net (code "202") (name "X_ROT_INPUT") (class "Default")
      (node (ref "CMP11") (pin "OUT_P") (pinfunction "P_OUT_P") (pintype "output"))
      (node (ref "CMP18") (pin "P$1") (pinfunction "A2_P$1") (pintype "input"))
      (node (ref "CMP34") (pin "P$2") (pinfunction "1_P$2") (pintype "input"))
    )
    (net (code "203") (name "unconnected-(CMP1-OUT_8-PadP$9)") (class "Default")
      (node (ref "CMP1") (pin "P$9") (pinfunction "OUT_8_P$9") (pintype "output"))
    )
    (net (code "204") (name "unconnected-(CMP1-OUT_9-PadP$10)") (class "Default")
      (node (ref "CMP1") (pin "P$10") (pinfunction "OUT_9_P$10") (pintype "output"))
    )
    (net (code "205") (name "unconnected-(CMP1-OUT_10-PadP$11)") (class "Default")
      (node (ref "CMP1") (pin "P$11") (pinfunction "OUT_10_P$11") (pintype "output"))
    )
    (net (code "206") (name "unconnected-(CMP1-OUT_11-PadP$12)") (class "Default")
      (node (ref "CMP1") (pin "P$12") (pinfunction "OUT_11_P$12") (pintype "output"))
    )
    (net (code "207") (name "unconnected-(CMP1-OUT_12-PadP$13)") (class "Default")
      (node (ref "CMP1") (pin "P$13") (pinfunction "OUT_12_P$13") (pintype "output"))
    )
    (net (code "208") (name "unconnected-(CMP1-OUT_13-PadP$14)") (class "Default")
      (node (ref "CMP1") (pin "P$14") (pinfunction "OUT_13_P$14") (pintype "output"))
    )
    (net (code "209") (name "unconnected-(CMP1-OUT_14-PadP$15)") (class "Default")
      (node (ref "CMP1") (pin "P$15") (pinfunction "OUT_14_P$15") (pintype "output"))
    )
    (net (code "210") (name "unconnected-(CMP1-OUT_15-PadP$16)") (class "Default")
      (node (ref "CMP1") (pin "P$16") (pinfunction "OUT_15_P$16") (pintype "output"))
    )
    (net (code "211") (name "unconnected-(CMP2-N-PadOUT_M)") (class "Default")
      (node (ref "CMP2") (pin "OUT_M") (pinfunction "N_OUT_M") (pintype "output"))
    )
    (net (code "212") (name "unconnected-(CMP3-N-PadOUT_M)") (class "Default")
      (node (ref "CMP3") (pin "OUT_M") (pinfunction "N_OUT_M") (pintype "output"))
    )
    (net (code "213") (name "unconnected-(CMP4-N-PadOUT_M)") (class "Default")
      (node (ref "CMP4") (pin "OUT_M") (pinfunction "N_OUT_M") (pintype "output"))
    )
    (net (code "214") (name "unconnected-(CMP5-N-PadOUT_M)") (class "Default")
      (node (ref "CMP5") (pin "OUT_M") (pinfunction "N_OUT_M") (pintype "output"))
    )
    (net (code "215") (name "unconnected-(CMP7-N-PadOUT_M)") (class "Default")
      (node (ref "CMP7") (pin "OUT_M") (pinfunction "N_OUT_M") (pintype "output"))
    )
    (net (code "216") (name "unconnected-(CMP8-N-PadOUT_M)") (class "Default")
      (node (ref "CMP8") (pin "OUT_M") (pinfunction "N_OUT_M") (pintype "output"))
    )
    (net (code "217") (name "unconnected-(CMP9-N-PadOUT_M)") (class "Default")
      (node (ref "CMP9") (pin "OUT_M") (pinfunction "N_OUT_M") (pintype "output"))
    )
    (net (code "218") (name "unconnected-(CMP10-PadE)") (class "Default")
      (node (ref "CMP10") (pin "E") (pinfunction "E_E") (pintype "input"))
    )
    (net (code "219") (name "unconnected-(CMP10-PadN0)") (class "Default")
      (node (ref "CMP10") (pin "N0") (pinfunction "N0_N0") (pintype "output"))
    )
    (net (code "220") (name "unconnected-(CMP10-PadN1)") (class "Default")
      (node (ref "CMP10") (pin "N1") (pinfunction "N1_N1") (pintype "output"))
    )
    (net (code "221") (name "unconnected-(CMP10-PadN3)") (class "Default")
      (node (ref "CMP10") (pin "N3") (pinfunction "N3_N3") (pintype "output"))
    )
    (net (code "222") (name "unconnected-(CMP11-N-PadOUT_M)") (class "Default")
      (node (ref "CMP11") (pin "OUT_M") (pinfunction "N_OUT_M") (pintype "output"))
    )
    (net (code "223") (name "unconnected-(CMP14-N-PadOUT_M)") (class "Default")
      (node (ref "CMP14") (pin "OUT_M") (pinfunction "N_OUT_M") (pintype "output"))
    )
    (net (code "224") (name "unconnected-(CMP15-OUT_3-PadP$4)") (class "Default")
      (node (ref "CMP15") (pin "P$4") (pinfunction "OUT_3_P$4") (pintype "output"))
    )
    (net (code "225") (name "unconnected-(CMP15-OUT_4-PadP$5)") (class "Default")
      (node (ref "CMP15") (pin "P$5") (pinfunction "OUT_4_P$5") (pintype "output"))
    )
    (net (code "226") (name "unconnected-(CMP15-OUT_5-PadP$6)") (class "Default")
      (node (ref "CMP15") (pin "P$6") (pinfunction "OUT_5_P$6") (pintype "output"))
    )
    (net (code "227") (name "unconnected-(CMP15-OUT_6-PadP$7)") (class "Default")
      (node (ref "CMP15") (pin "P$7") (pinfunction "OUT_6_P$7") (pintype "output"))
    )
    (net (code "228") (name "unconnected-(CMP15-OUT_7-PadP$8)") (class "Default")
      (node (ref "CMP15") (pin "P$8") (pinfunction "OUT_7_P$8") (pintype "output"))
    )
    (net (code "229") (name "unconnected-(CMP15-OUT_8-PadP$9)") (class "Default")
      (node (ref "CMP15") (pin "P$9") (pinfunction "OUT_8_P$9") (pintype "output"))
    )
    (net (code "230") (name "unconnected-(CMP15-OUT_9-PadP$10)") (class "Default")
      (node (ref "CMP15") (pin "P$10") (pinfunction "OUT_9_P$10") (pintype "output"))
    )
    (net (code "231") (name "unconnected-(CMP15-OUT_10-PadP$11)") (class "Default")
      (node (ref "CMP15") (pin "P$11") (pinfunction "OUT_10_P$11") (pintype "output"))
    )
    (net (code "232") (name "unconnected-(CMP15-OUT_11-PadP$12)") (class "Default")
      (node (ref "CMP15") (pin "P$12") (pinfunction "OUT_11_P$12") (pintype "output"))
    )
    (net (code "233") (name "unconnected-(CMP15-OUT_12-PadP$13)") (class "Default")
      (node (ref "CMP15") (pin "P$13") (pinfunction "OUT_12_P$13") (pintype "output"))
    )
    (net (code "234") (name "unconnected-(CMP15-OUT_13-PadP$14)") (class "Default")
      (node (ref "CMP15") (pin "P$14") (pinfunction "OUT_13_P$14") (pintype "output"))
    )
    (net (code "235") (name "unconnected-(CMP15-OUT_14-PadP$15)") (class "Default")
      (node (ref "CMP15") (pin "P$15") (pinfunction "OUT_14_P$15") (pintype "output"))
    )
    (net (code "236") (name "unconnected-(CMP15-OUT_15-PadP$16)") (class "Default")
      (node (ref "CMP15") (pin "P$16") (pinfunction "OUT_15_P$16") (pintype "output"))
    )
    (net (code "237") (name "unconnected-(CMP16-N-PadOUT_M)") (class "Default")
      (node (ref "CMP16") (pin "OUT_M") (pinfunction "N_OUT_M") (pintype "output"))
    )
    (net (code "238") (name "unconnected-(CMP17-P-PadOUT_P)") (class "Default")
      (node (ref "CMP17") (pin "OUT_P") (pinfunction "P_OUT_P") (pintype "output"))
    )
    (net (code "239") (name "unconnected-(CMP18-N-PadOUT_M)") (class "Default")
      (node (ref "CMP18") (pin "OUT_M") (pinfunction "N_OUT_M") (pintype "output"))
    )
    (net (code "240") (name "unconnected-(CMP19-N-PadOUT_M)") (class "Default")
      (node (ref "CMP19") (pin "OUT_M") (pinfunction "N_OUT_M") (pintype "output"))
    )
    (net (code "241") (name "unconnected-(CMP20-N-PadOUT_M)") (class "Default")
      (node (ref "CMP20") (pin "OUT_M") (pinfunction "N_OUT_M") (pintype "output"))
    )
    (net (code "242") (name "unconnected-(CMP21-OUT_7-PadP$8)") (class "Default")
      (node (ref "CMP21") (pin "P$8") (pinfunction "OUT_7_P$8") (pintype "output"))
    )
    (net (code "243") (name "unconnected-(CMP21-OUT_15-PadP$16)") (class "Default")
      (node (ref "CMP21") (pin "P$16") (pinfunction "OUT_15_P$16") (pintype "output"))
    )
    (net (code "244") (name "unconnected-(CMP22-OUT_6-PadP$7)") (class "Default")
      (node (ref "CMP22") (pin "P$7") (pinfunction "OUT_6_P$7") (pintype "output"))
    )
    (net (code "245") (name "unconnected-(CMP22-OUT_7-PadP$8)") (class "Default")
      (node (ref "CMP22") (pin "P$8") (pinfunction "OUT_7_P$8") (pintype "output"))
    )
    (net (code "246") (name "unconnected-(CMP22-OUT_8-PadP$9)") (class "Default")
      (node (ref "CMP22") (pin "P$9") (pinfunction "OUT_8_P$9") (pintype "output"))
    )
    (net (code "247") (name "unconnected-(CMP22-OUT_9-PadP$10)") (class "Default")
      (node (ref "CMP22") (pin "P$10") (pinfunction "OUT_9_P$10") (pintype "output"))
    )
    (net (code "248") (name "unconnected-(CMP22-OUT_10-PadP$11)") (class "Default")
      (node (ref "CMP22") (pin "P$11") (pinfunction "OUT_10_P$11") (pintype "output"))
    )
    (net (code "249") (name "unconnected-(CMP22-OUT_11-PadP$12)") (class "Default")
      (node (ref "CMP22") (pin "P$12") (pinfunction "OUT_11_P$12") (pintype "output"))
    )
    (net (code "250") (name "unconnected-(CMP22-OUT_12-PadP$13)") (class "Default")
      (node (ref "CMP22") (pin "P$13") (pinfunction "OUT_12_P$13") (pintype "output"))
    )
    (net (code "251") (name "unconnected-(CMP22-OUT_13-PadP$14)") (class "Default")
      (node (ref "CMP22") (pin "P$14") (pinfunction "OUT_13_P$14") (pintype "output"))
    )
    (net (code "252") (name "unconnected-(CMP22-OUT_14-PadP$15)") (class "Default")
      (node (ref "CMP22") (pin "P$15") (pinfunction "OUT_14_P$15") (pintype "output"))
    )
    (net (code "253") (name "unconnected-(CMP22-OUT_15-PadP$16)") (class "Default")
      (node (ref "CMP22") (pin "P$16") (pinfunction "OUT_15_P$16") (pintype "output"))
    )
    (net (code "254") (name "unconnected-(CMP23-N-PadOUT_M)") (class "Default")
      (node (ref "CMP23") (pin "OUT_M") (pinfunction "N_OUT_M") (pintype "output"))
    )
    (net (code "255") (name "unconnected-(CMP24-P-PadOUT_P)") (class "Default")
      (node (ref "CMP24") (pin "OUT_P") (pinfunction "P_OUT_P") (pintype "output"))
    )
    (net (code "256") (name "unconnected-(CMP25-PadP)") (class "Default")
      (node (ref "CMP25") (pin "P") (pinfunction "P_P") (pintype "output"))
    )
    (net (code "257") (name "unconnected-(CMP26-N-PadOUT_M)") (class "Default")
      (node (ref "CMP26") (pin "OUT_M") (pinfunction "N_OUT_M") (pintype "output"))
    )
    (net (code "258") (name "unconnected-(CMP28-N-PadOUT_M)") (class "Default")
      (node (ref "CMP28") (pin "OUT_M") (pinfunction "N_OUT_M") (pintype "output"))
    )
    (net (code "259") (name "unconnected-(CMP29-N-PadOUT_M)") (class "Default")
      (node (ref "CMP29") (pin "OUT_M") (pinfunction "N_OUT_M") (pintype "output"))
    )
    (net (code "260") (name "unconnected-(CMP30-N-PadOUT_M)") (class "Default")
      (node (ref "CMP30") (pin "OUT_M") (pinfunction "N_OUT_M") (pintype "output"))
    )
    (net (code "261") (name "unconnected-(CMP31-N-PadOUT_M)") (class "Default")
      (node (ref "CMP31") (pin "OUT_M") (pinfunction "N_OUT_M") (pintype "output"))
    )
    (net (code "262") (name "unconnected-(CMP32-N-PadOUT_M)") (class "Default")
      (node (ref "CMP32") (pin "OUT_M") (pinfunction "N_OUT_M") (pintype "output"))
    )
    (net (code "263") (name "unconnected-(CMP33-N-PadOUT_M)") (class "Default")
      (node (ref "CMP33") (pin "OUT_M") (pinfunction "N_OUT_M") (pintype "output"))
    )
    (net (code "264") (name "unconnected-(CMP34-N-PadOUT_M)") (class "Default")
      (node (ref "CMP34") (pin "OUT_M") (pinfunction "N_OUT_M") (pintype "output"))
    )
    (net (code "265") (name "unconnected-(CMP35-PadE)") (class "Default")
      (node (ref "CMP35") (pin "E") (pinfunction "E_E") (pintype "input"))
    )
    (net (code "266") (name "unconnected-(CMP35-PadN0)") (class "Default")
      (node (ref "CMP35") (pin "N0") (pinfunction "N0_N0") (pintype "output"))
    )
    (net (code "267") (name "unconnected-(CMP35-PadN1)") (class "Default")
      (node (ref "CMP35") (pin "N1") (pinfunction "N1_N1") (pintype "output"))
    )
    (net (code "268") (name "unconnected-(CMP35-PadN2)") (class "Default")
      (node (ref "CMP35") (pin "N2") (pinfunction "N2_N2") (pintype "output"))
    )
    (net (code "269") (name "unconnected-(CMP35-PadN3)") (class "Default")
      (node (ref "CMP35") (pin "N3") (pinfunction "N3_N3") (pintype "output"))
    )
    (net (code "270") (name "unconnected-(CMP35-PadN4)") (class "Default")
      (node (ref "CMP35") (pin "N4") (pinfunction "N4_N4") (pintype "output"))
    )
    (net (code "271") (name "unconnected-(CMP35-PadN5)") (class "Default")
      (node (ref "CMP35") (pin "N5") (pinfunction "N5_N5") (pintype "output"))
    )
    (net (code "272") (name "unconnected-(CMP35-PadN6)") (class "Default")
      (node (ref "CMP35") (pin "N6") (pinfunction "N6_N6") (pintype "output"))
    )
    (net (code "273") (name "unconnected-(CMP35-PadN7)") (class "Default")
      (node (ref "CMP35") (pin "N7") (pinfunction "N7_N7") (pintype "output"))
    )
    (net (code "274") (name "unconnected-(CMP35-PadN8)") (class "Default")
      (node (ref "CMP35") (pin "N8") (pinfunction "N8_N8") (pintype "output"))
    )
    (net (code "275") (name "unconnected-(CMP35-PadN9)") (class "Default")
      (node (ref "CMP35") (pin "N9") (pinfunction "N9_N9") (pintype "output"))
    )
    (net (code "276") (name "unconnected-(CMP35-PadN10)") (class "Default")
      (node (ref "CMP35") (pin "N10") (pinfunction "N10_N10") (pintype "output"))
    )
    (net (code "277") (name "unconnected-(CMP35-PadN11)") (class "Default")
      (node (ref "CMP35") (pin "N11") (pinfunction "N11_N11") (pintype "output"))
    )
    (net (code "278") (name "unconnected-(CMP35-PadN12)") (class "Default")
      (node (ref "CMP35") (pin "N12") (pinfunction "N12_N12") (pintype "output"))
    )
    (net (code "279") (name "unconnected-(CMP35-PadN13)") (class "Default")
      (node (ref "CMP35") (pin "N13") (pinfunction "N13_N13") (pintype "output"))
    )
    (net (code "280") (name "unconnected-(CMP35-PadN14)") (class "Default")
      (node (ref "CMP35") (pin "N14") (pinfunction "N14_N14") (pintype "output"))
    )
    (net (code "281") (name "unconnected-(CMP35-PadN15)") (class "Default")
      (node (ref "CMP35") (pin "N15") (pinfunction "N15_N15") (pintype "output"))
    )
    (net (code "282") (name "unconnected-(CMP36-M-PadOUT_M)") (class "Default")
      (node (ref "CMP36") (pin "OUT_M") (pinfunction "M_OUT_M") (pintype "output"))
    )
    (net (code "283") (name "unconnected-(CMP37-M-PadOUT_M)") (class "Default")
      (node (ref "CMP37") (pin "OUT_M") (pinfunction "M_OUT_M") (pintype "output"))
    )
    (net (code "284") (name "unconnected-(CMP40-OUT-PadP$2)") (class "Default")
      (node (ref "CMP40") (pin "P$2") (pinfunction "OUT_P$2") (pintype "output"))
    )
    (net (code "285") (name "unconnected-(CMP41-PadP)") (class "Default")
      (node (ref "CMP41") (pin "P") (pinfunction "P_P") (pintype "output"))
    )
    (net (code "286") (name "unconnected-(CMP42-N-PadOUT_M)") (class "Default")
      (node (ref "CMP42") (pin "OUT_M") (pinfunction "N_OUT_M") (pintype "output"))
    )
    (net (code "287") (name "unconnected-(CMP43-N-PadOUT_M)") (class "Default")
      (node (ref "CMP43") (pin "OUT_M") (pinfunction "N_OUT_M") (pintype "output"))
    )
    (net (code "288") (name "unconnected-(CMP44-P-PadOUT_P)") (class "Default")
      (node (ref "CMP44") (pin "OUT_P") (pinfunction "P_OUT_P") (pintype "output"))
    )
    (net (code "289") (name "unconnected-(CMP45-N-PadOUT_M)") (class "Default")
      (node (ref "CMP45") (pin "OUT_M") (pinfunction "N_OUT_M") (pintype "output"))
    )
    (net (code "290") (name "unconnected-(CMP46-P-PadOUT_P)") (class "Default")
      (node (ref "CMP46") (pin "OUT_P") (pinfunction "P_OUT_P") (pintype "output"))
    )
    (net (code "291") (name "unconnected-(CMP47-N-PadOUT_M)") (class "Default")
      (node (ref "CMP47") (pin "OUT_M") (pinfunction "N_OUT_M") (pintype "output"))
    )
    (net (code "292") (name "unconnected-(CMP48-N-PadOUT_M)") (class "Default")
      (node (ref "CMP48") (pin "OUT_M") (pinfunction "N_OUT_M") (pintype "output"))
    )
    (net (code "293") (name "unconnected-(CMP49-N-PadOUT_M)") (class "Default")
      (node (ref "CMP49") (pin "OUT_M") (pinfunction "N_OUT_M") (pintype "output"))
    )
    (net (code "294") (name "unconnected-(CMP50-N-PadOUT_M)") (class "Default")
      (node (ref "CMP50") (pin "OUT_M") (pinfunction "N_OUT_M") (pintype "output"))
    )
    (net (code "295") (name "unconnected-(CMP51-N-PadOUT_M)") (class "Default")
      (node (ref "CMP51") (pin "OUT_M") (pinfunction "N_OUT_M") (pintype "output"))
    )
    (net (code "296") (name "unconnected-(CMP52-N-PadOUT_M)") (class "Default")
      (node (ref "CMP52") (pin "OUT_M") (pinfunction "N_OUT_M") (pintype "output"))
    )
    (net (code "297") (name "unconnected-(CMP53-N-PadOUT_M)") (class "Default")
      (node (ref "CMP53") (pin "OUT_M") (pinfunction "N_OUT_M") (pintype "output"))
    )
    (net (code "298") (name "unconnected-(CMP54-P-PadOUT_P)") (class "Default")
      (node (ref "CMP54") (pin "OUT_P") (pinfunction "P_OUT_P") (pintype "output"))
    )
    (net (code "299") (name "unconnected-(CMP55-N-PadOUT_M)") (class "Default")
      (node (ref "CMP55") (pin "OUT_M") (pinfunction "N_OUT_M") (pintype "output"))
    )
    (net (code "300") (name "unconnected-(CMP56-M-PadOUT_M)") (class "Default")
      (node (ref "CMP56") (pin "OUT_M") (pinfunction "M_OUT_M") (pintype "output"))
    )
    (net (code "301") (name "unconnected-(CMP57-PadP)") (class "Default")
      (node (ref "CMP57") (pin "P") (pinfunction "P_P") (pintype "output"))
    )
    (net (code "302") (name "unconnected-(CMP59-M-PadOUT_M)") (class "Default")
      (node (ref "CMP59") (pin "OUT_M") (pinfunction "M_OUT_M") (pintype "output"))
    )
    (net (code "303") (name "unconnected-(CMP60-N-PadOUT_M)") (class "Default")
      (node (ref "CMP60") (pin "OUT_M") (pinfunction "N_OUT_M") (pintype "output"))
    )
    (net (code "304") (name "unconnected-(CMP61-N-PadOUT_M)") (class "Default")
      (node (ref "CMP61") (pin "OUT_M") (pinfunction "N_OUT_M") (pintype "output"))
    )
    (net (code "305") (name "unconnected-(CMP62-P-PadOUT_P)") (class "Default")
      (node (ref "CMP62") (pin "OUT_P") (pinfunction "P_OUT_P") (pintype "output"))
    )
    (net (code "306") (name "unconnected-(CMP65-IN_15-PadP$16)") (class "Default")
      (node (ref "CMP65") (pin "P$16") (pinfunction "IN_15_P$16") (pintype "input"))
    )
    (net (code "307") (name "unconnected-(CMP94-OUT_13-PadP$14)") (class "Default")
      (node (ref "CMP94") (pin "P$14") (pinfunction "OUT_13_P$14") (pintype "output"))
    )
    (net (code "308") (name "unconnected-(CMP94-OUT_14-PadP$15)") (class "Default")
      (node (ref "CMP94") (pin "P$15") (pinfunction "OUT_14_P$15") (pintype "output"))
    )
    (net (code "309") (name "unconnected-(CMP94-OUT_15-PadP$16)") (class "Default")
      (node (ref "CMP94") (pin "P$16") (pinfunction "OUT_15_P$16") (pintype "output"))
    )
  )
)
